# ETH_CAN_Sheet1.net
KiCad netlist of a schematic drawn in Altium Designer
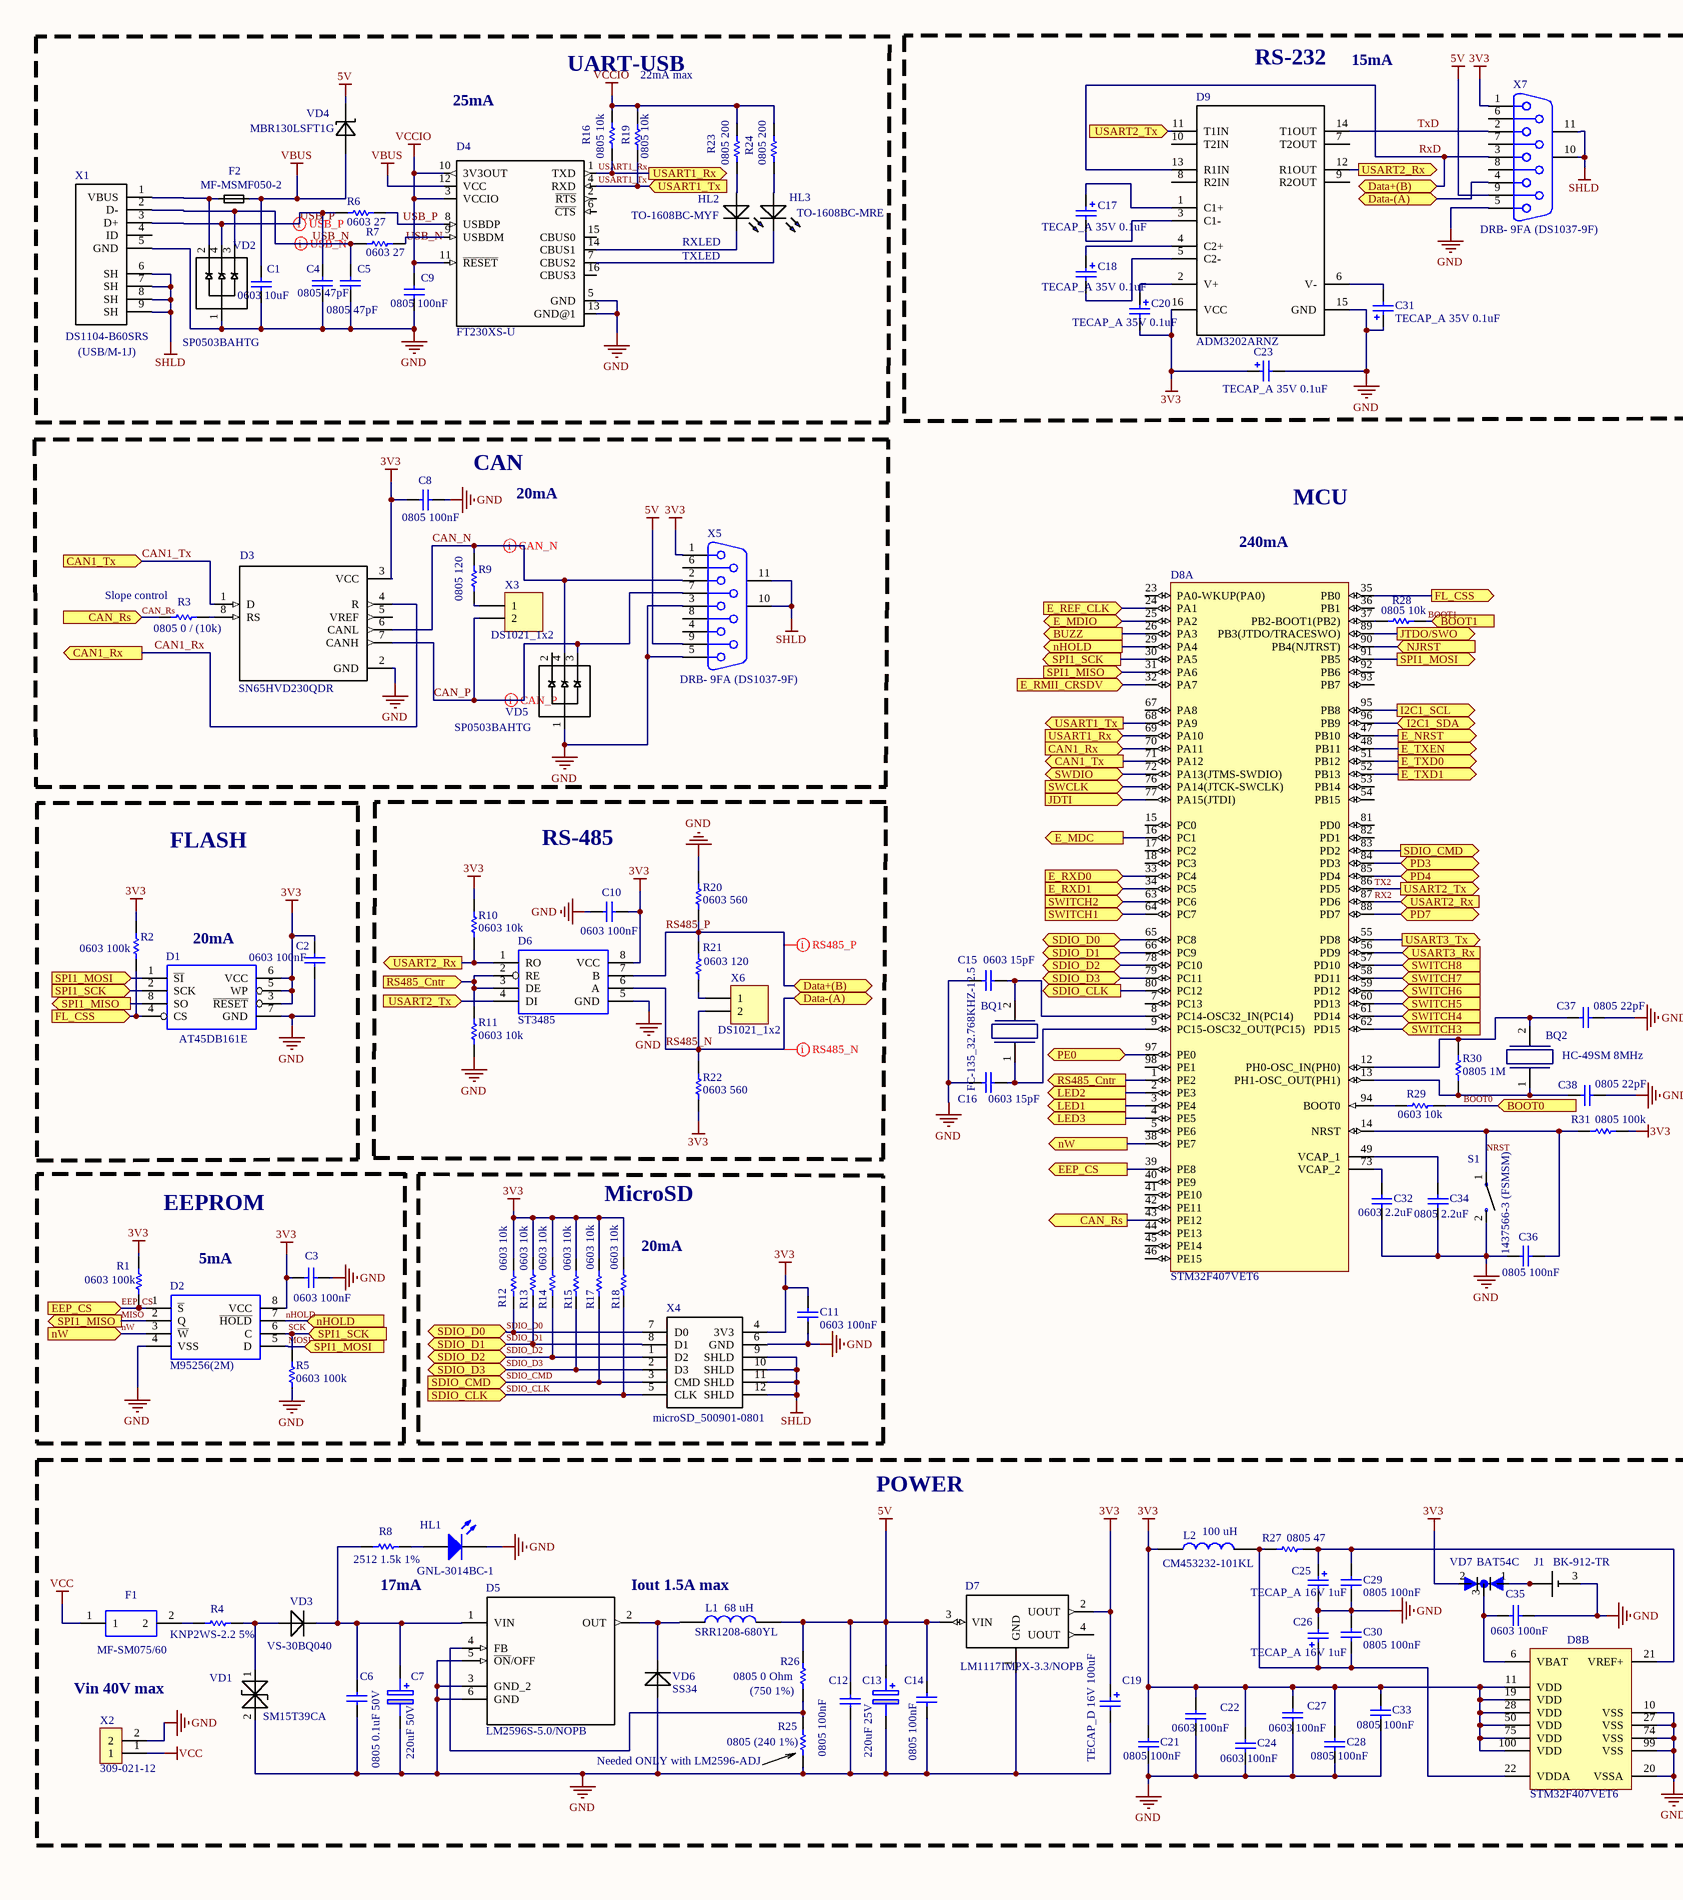
[diagram p0: ETH_CAN_Sheet1.SchDoc, left]
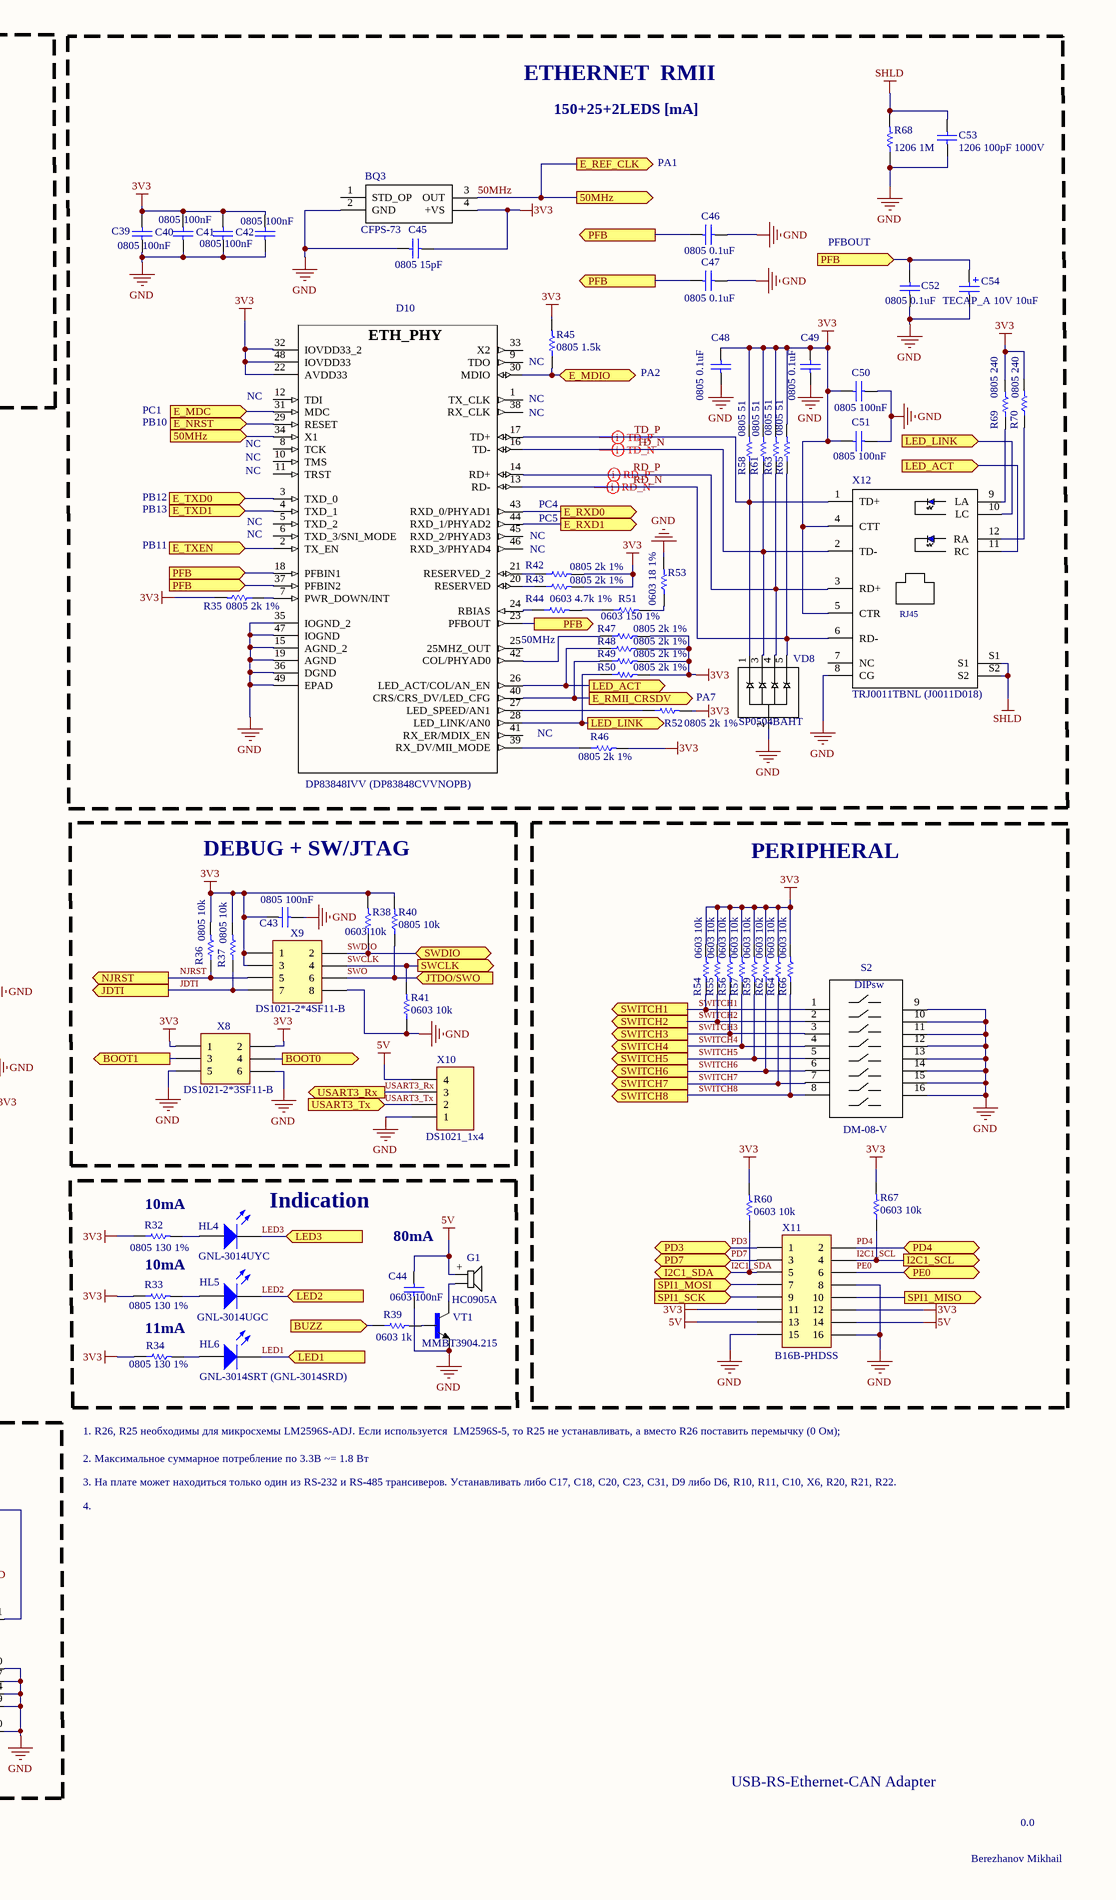
[diagram p1: ETH_CAN_Sheet1.SchDoc, right]

(export (version "E")
  (design (tool "Eeschema 10.0.6"))
  (components
    (comp (ref "BQ1")
      (value "FC-135_32.768KHZ-12.5")
      (footprint "FC-135")
      (description "Clock SMD Crystal")
      (libsource (lib "MyCompLib") (part "FC135-32768-7"))
    )
    (comp (ref "BQ2")
      (value "HC-49SM 8MHz")
      (footprint "HC49SM")
      (description "HC49SM")
      (libsource (lib "MyCompLib") (part "HC49SM"))
    )
    (comp (ref "BQ3")
      (value "CFPS-73")
      (footprint "CFPS-73")
      (description "IQD FREQUENCY PRODUCTS - SPXO018044-CFPS-73 - OSCILLATOR FREQUENCY, 50MHZ")
      (libsource (lib "MyCompLib") (part "SPXO018044CFPS-73"))
    )
    (comp (ref "C1")
      (value "0603 10uF")
      (footprint "C_SMD0603")
      (description "SMD Cap 0603")
      (libsource (lib "MyCompLib") (part "C0603"))
    )
    (comp (ref "C2")
      (value "0603 100nF")
      (footprint "C_SMD0603")
      (description "SMD Cap 0603")
      (libsource (lib "MyCompLib") (part "C0603"))
    )
    (comp (ref "C3")
      (value "0603 100nF")
      (footprint "C_SMD0603")
      (description "SMD Cap 0603")
      (libsource (lib "MyCompLib") (part "C0603"))
    )
    (comp (ref "C4")
      (value "0805 47pF")
      (footprint "C_SMD0805")
      (description "SMD Cap 0805")
      (fields (field (name "PUBLISHER") "Altium Limited"))
      (libsource (lib "MyCompLib") (part "C0805"))
    )
    (comp (ref "C5")
      (value "0805 47pF")
      (footprint "C_SMD0805")
      (description "SMD Cap 0805")
      (fields (field (name "PUBLISHER") "Altium Limited"))
      (libsource (lib "MyCompLib") (part "C0805"))
    )
    (comp (ref "C6")
      (value "0805 0.1uF 50V")
      (footprint "C_SMD0805")
      (description "SMD Cap 0805")
      (fields (field (name "PUBLISHER") "Altium Limited"))
      (libsource (lib "MyCompLib") (part "C0805"))
    )
    (comp (ref "C7")
      (value "220uF 50V")
      (footprint "SMD_ELC_CAP")
      (fields
        (field (name "MANUFACTURER_PART_NUMBER") "EEEFK1H221P")
        (field (name "RS PART NUMBER") "6294598")
      )
      (libsource (lib "MyCompLib") (part "EEEFK1H221P"))
    )
    (comp (ref "C8")
      (value "0805 100nF")
      (footprint "C_SMD0805")
      (description "SMD Cap 0805")
      (fields (field (name "PUBLISHER") "Altium Limited"))
      (libsource (lib "MyCompLib") (part "C0805"))
    )
    (comp (ref "C9")
      (value "0805 100nF")
      (footprint "C_SMD0805")
      (description "SMD Cap 0805")
      (fields (field (name "PUBLISHER") "Altium Limited"))
      (libsource (lib "MyCompLib") (part "C0805"))
    )
    (comp (ref "C10")
      (value "0603 100nF")
      (footprint "C_SMD0603")
      (description "SMD Cap 0603")
      (libsource (lib "MyCompLib") (part "C0603"))
    )
    (comp (ref "C11")
      (value "0603 100nF")
      (footprint "C_SMD0603")
      (description "SMD Cap 0603")
      (libsource (lib "MyCompLib") (part "C0603"))
    )
    (comp (ref "C12")
      (value "0805 100nF")
      (footprint "C_SMD0805")
      (description "SMD Cap 0805")
      (fields (field (name "PUBLISHER") "Altium Limited"))
      (libsource (lib "MyCompLib") (part "C0805"))
    )
    (comp (ref "C13")
      (value "220uF 25V")
      (footprint "SMD_ELC_CAP")
      (fields
        (field (name "MANUFACTURER_PART_NUMBER") "EEEFK1H221P")
        (field (name "RS PART NUMBER") "6294598")
      )
      (libsource (lib "MyCompLib") (part "EEEFK1H221P"))
    )
    (comp (ref "C14")
      (value "0805 100nF")
      (footprint "C_SMD0805")
      (description "SMD Cap 0805")
      (libsource (lib "") (part "C0805_1"))
    )
    (comp (ref "C15")
      (value "0603 15pF")
      (footprint "C_SMD0603")
      (description "SMD Cap 0603")
      (libsource (lib "MyCompLib") (part "C0603"))
    )
    (comp (ref "C16")
      (value "0603 15pF")
      (footprint "C_SMD0603")
      (description "SMD Cap 0603")
      (libsource (lib "MyCompLib") (part "C0603"))
    )
    (comp (ref "C17")
      (value "TECAP_A 35V 0.1uF")
      (footprint "TECAP_A")
      (description "Tantalum pol cap type A")
      (libsource (lib "MyCompLib") (part "TECAP_A"))
    )
    (comp (ref "C18")
      (value "TECAP_A 35V 0.1uF")
      (footprint "TECAP_A")
      (description "Tantalum pol cap type A")
      (libsource (lib "MyCompLib") (part "TECAP_A"))
    )
    (comp (ref "C19")
      (value "TECAP_D 16V 100uF")
      (footprint "TECAP_D")
      (description "Tantalum pol cap type D")
      (libsource (lib "MyCompLib") (part "TECAP_D"))
    )
    (comp (ref "C20")
      (value "TECAP_A 35V 0.1uF")
      (footprint "TECAP_A")
      (description "Tantalum pol cap type A")
      (libsource (lib "MyCompLib") (part "TECAP_A"))
    )
    (comp (ref "C21")
      (value "0805 100nF")
      (footprint "C_SMD0805")
      (description "SMD Cap 0805")
      (fields (field (name "PUBLISHER") "Altium Limited"))
      (libsource (lib "MyCompLib") (part "C0805"))
    )
    (comp (ref "C22")
      (value "0603 100nF")
      (footprint "C_SMD0603")
      (description "SMD Cap 0603")
      (libsource (lib "MyCompLib") (part "C0603"))
    )
    (comp (ref "C23")
      (value "TECAP_A 35V 0.1uF")
      (footprint "TECAP_A")
      (description "Tantalum pol cap type A")
      (libsource (lib "MyCompLib") (part "TECAP_A"))
    )
    (comp (ref "C24")
      (value "0603 100nF")
      (footprint "C_SMD0603")
      (description "SMD Cap 0603")
      (libsource (lib "MyCompLib") (part "C0603"))
    )
    (comp (ref "C25")
      (value "TECAP_A 16V 1uF")
      (footprint "TECAP_A")
      (description "Tantalum pol cap type A")
      (libsource (lib "MyCompLib") (part "TECAP_A"))
    )
    (comp (ref "C26")
      (value "TECAP_A 16V 1uF")
      (footprint "TECAP_A")
      (description "Tantalum pol cap type A")
      (libsource (lib "MyCompLib") (part "TECAP_A"))
    )
    (comp (ref "C27")
      (value "0603 100nF")
      (footprint "C_SMD0603")
      (description "SMD Cap 0603")
      (libsource (lib "MyCompLib") (part "C0603"))
    )
    (comp (ref "C28")
      (value "0805 100nF")
      (footprint "C_SMD0805")
      (description "SMD Cap 0805")
      (fields (field (name "PUBLISHER") "Altium Limited"))
      (libsource (lib "MyCompLib") (part "C0805"))
    )
    (comp (ref "C29")
      (value "0805 100nF")
      (footprint "C_SMD0805")
      (description "SMD Cap 0805")
      (fields (field (name "PUBLISHER") "Altium Limited"))
      (libsource (lib "MyCompLib") (part "C0805"))
    )
    (comp (ref "C30")
      (value "0805 100nF")
      (footprint "C_SMD0805")
      (description "SMD Cap 0805")
      (fields (field (name "PUBLISHER") "Altium Limited"))
      (libsource (lib "MyCompLib") (part "C0805"))
    )
    (comp (ref "C31")
      (value "TECAP_A 35V 0.1uF")
      (footprint "TECAP_A")
      (description "Tantalum pol cap type A")
      (libsource (lib "MyCompLib") (part "TECAP_A"))
    )
    (comp (ref "C32")
      (value "0603 2.2uF")
      (footprint "C_SMD0603")
      (description "SMD Cap 0603")
      (libsource (lib "MyCompLib") (part "C0603"))
    )
    (comp (ref "C33")
      (value "0805 100nF")
      (footprint "C_SMD0805")
      (description "SMD Cap 0805")
      (fields (field (name "PUBLISHER") "Altium Limited"))
      (libsource (lib "MyCompLib") (part "C0805"))
    )
    (comp (ref "C34")
      (value "0805 2.2uF")
      (footprint "C_SMD0805")
      (description "SMD Cap 0805")
      (fields (field (name "PUBLISHER") "Altium Limited"))
      (libsource (lib "MyCompLib") (part "C0805"))
    )
    (comp (ref "C35")
      (value "0603 100nF")
      (footprint "C_SMD0603")
      (description "SMD Cap 0603")
      (libsource (lib "MyCompLib") (part "C0603"))
    )
    (comp (ref "C36")
      (value "0805 100nF")
      (footprint "C_SMD0805")
      (description "SMD Cap 0805")
      (fields (field (name "PUBLISHER") "Altium Limited"))
      (libsource (lib "MyCompLib") (part "C0805"))
    )
    (comp (ref "C37")
      (value "0805 22pF")
      (footprint "C_SMD0805")
      (description "SMD Cap 0805")
      (fields (field (name "PUBLISHER") "Altium Limited"))
      (libsource (lib "MyCompLib") (part "C0805"))
    )
    (comp (ref "C38")
      (value "0805 22pF")
      (footprint "C_SMD0805")
      (description "SMD Cap 0805")
      (fields (field (name "PUBLISHER") "Altium Limited"))
      (libsource (lib "MyCompLib") (part "C0805"))
    )
    (comp (ref "C39")
      (value "0805 100nF")
      (footprint "C_SMD0805")
      (description "SMD Cap 0805")
      (fields (field (name "PUBLISHER") "Altium Limited"))
      (libsource (lib "MyCompLib") (part "C0805"))
    )
    (comp (ref "C40")
      (value "0805 100nF")
      (footprint "C_SMD0805")
      (description "SMD Cap 0805")
      (fields (field (name "PUBLISHER") "Altium Limited"))
      (libsource (lib "MyCompLib") (part "C0805"))
    )
    (comp (ref "C41")
      (value "0805 100nF")
      (footprint "C_SMD0805")
      (description "SMD Cap 0805")
      (fields (field (name "PUBLISHER") "Altium Limited"))
      (libsource (lib "MyCompLib") (part "C0805"))
    )
    (comp (ref "C42")
      (value "0805 100nF")
      (footprint "C_SMD0805")
      (description "SMD Cap 0805")
      (fields (field (name "PUBLISHER") "Altium Limited"))
      (libsource (lib "MyCompLib") (part "C0805"))
    )
    (comp (ref "C43")
      (value "0805 100nF")
      (footprint "C_SMD0805")
      (description "SMD Cap 0805")
      (fields (field (name "PUBLISHER") "Altium Limited"))
      (libsource (lib "MyCompLib") (part "C0805"))
    )
    (comp (ref "C44")
      (value "0603 100nF")
      (footprint "C_SMD0603")
      (description "SMD Cap 0603")
      (libsource (lib "MyCompLib") (part "C0603"))
    )
    (comp (ref "C45")
      (value "0805 15pF")
      (footprint "C_SMD0805")
      (description "SMD Cap 0805")
      (fields (field (name "PUBLISHER") "Altium Limited"))
      (libsource (lib "MyCompLib") (part "C0805"))
    )
    (comp (ref "C46")
      (value "0805 0.1uF")
      (footprint "C_SMD0805")
      (description "SMD Cap 0805")
      (fields (field (name "PUBLISHER") "Altium Limited"))
      (libsource (lib "MyCompLib") (part "C0805"))
    )
    (comp (ref "C47")
      (value "0805 0.1uF")
      (footprint "C_SMD0805")
      (description "SMD Cap 0805")
      (fields (field (name "PUBLISHER") "Altium Limited"))
      (libsource (lib "MyCompLib") (part "C0805"))
    )
    (comp (ref "C48")
      (value "0805 0.1uF")
      (footprint "C_SMD0805")
      (description "SMD Cap 0805")
      (fields (field (name "PUBLISHER") "Altium Limited"))
      (libsource (lib "MyCompLib") (part "C0805"))
    )
    (comp (ref "C49")
      (value "0805 0.1uF")
      (footprint "C_SMD0805")
      (description "SMD Cap 0805")
      (fields (field (name "PUBLISHER") "Altium Limited"))
      (libsource (lib "MyCompLib") (part "C0805"))
    )
    (comp (ref "C50")
      (value "0805 100nF")
      (footprint "C_SMD0805")
      (description "SMD Cap 0805")
      (fields (field (name "PUBLISHER") "Altium Limited"))
      (libsource (lib "MyCompLib") (part "C0805"))
    )
    (comp (ref "C51")
      (value "0805 100nF")
      (footprint "C_SMD0805")
      (description "SMD Cap 0805")
      (fields (field (name "PUBLISHER") "Altium Limited"))
      (libsource (lib "MyCompLib") (part "C0805"))
    )
    (comp (ref "C52")
      (value "0805 0.1uF")
      (footprint "C_SMD0805")
      (description "SMD Cap 0805")
      (fields (field (name "PUBLISHER") "Altium Limited"))
      (libsource (lib "MyCompLib") (part "C0805"))
    )
    (comp (ref "C53")
      (value "1206 100pF 1000V")
      (footprint "CAP SMD1206")
      (description "SMD Cap 1206")
      (fields (field (name "PUBLISHER") "Altium Limited"))
      (libsource (lib "MyCompLib") (part "C1206"))
    )
    (comp (ref "C54")
      (value "TECAP_A 10V 10uF")
      (footprint "TECAP_A")
      (description "Tantalum pol cap type A")
      (libsource (lib "MyCompLib") (part "TECAP_A"))
    )
    (comp (ref "D1")
      (value "AT45DB161E")
      (footprint "SOIC8 (SO-8)")
      (description "SPI FLASH 16Mbit(528 bytes x 4096 pages)")
      (libsource (lib "MyCompLib") (part "AT45DB161E"))
    )
    (comp (ref "D2")
      (value "M95256(2M)")
      (footprint "SOIC8 (SO-8)")
      (description "M95256-WMN6TP, Serial EEPROM Memory 256kbit, Serial-SPI, 60ns 2.5  5.5 V, 8-Pin SOIC")
      (libsource (lib "MyCompLib") (part "M95256(2M)-WMN6TP"))
    )
    (comp (ref "D3")
      (value "SN65HVD230QDR")
      (footprint "SOIC-12")
      (description "3.3-V CAN Transceiver with Standby Mode 8-SOIC -40 to 125")
      (fields (field (name "MF") "Texas Instruments"))
      (libsource (lib "MyCompLib") (part "SN65HVD230QDR"))
    )
    (comp (ref "D4")
      (value "FT230XS-U")
      (footprint "SSOP16")
      (description "FT230XS-U, USB Controller, 3MBd, USB 1.1, USB 2.0, 5 V, 16-Pin SSOP")
      (fields (field (name "MF") "FTDI,"))
      (libsource (lib "MyCompLib") (part "FT230XS-U"))
    )
    (comp (ref "D5")
      (value "LM2596S-5.0/NOPB")
      (footprint "TO263-5")
      (description "SIMPLE SWITCHER&#174; 4.5V to 40V, 3A Low Component Count Step-Down Regulator")
      (libsource (lib "MyCompLib") (part "LM2596S"))
    )
    (comp (ref "D6")
      (value "ST3485")
      (footprint "SOIC8 (SO-8)")
      (description "3.3 V low power transceiver for RS-485")
      (libsource (lib "MyCompLib") (part "ST3485"))
    )
    (comp (ref "D7")
      (value "LM1117IMPX-3.3/NOPB")
      (footprint "SOT223")
      (description "Линейный регулятор с низким падением напряжения, 3.3В")
      (libsource (lib "MyCompLib") (part "LM1117-3.3"))
    )
    (comp (ref "D8")
      (value "STM32F407VET6")
      (footprint "STM-LQFP100_N")
      (fields (field (name "MANUFACTURER") "STMicroelectronics"))
      (libsource (lib "STMicroelectronics STM32 F4") (part "STM32F407VET6"))
    )
    (comp (ref "D9")
      (value "ADM3202ARNZ")
      (footprint "SOIC-16")
      (description "3.3V SMD RS232-UART")
      (libsource (lib "MyCompLib") (part "ADM3202ARNZ"))
    )
    (comp (ref "D10")
      (value "DP83848IVV (DP83848CVVNOPB)")
      (footprint "QFP48")
      (description "ETH Transciever")
      (libsource (lib "MyCompLib") (part "DP83848CVVNOPB"))
    )
    (comp (ref "F1")
      (value "MF-SM075/60")
      (footprint "MF-SM075/60")
      (libsource (lib "MyCompLib") (part "MF-SM075/60"))
    )
    (comp (ref "F2")
      (value "MF-MSMF050-2")
      (footprint "FUSE1812x0")
      (description "PTC Resettable Fuse 0.5A_hold_ 1A_trip_ 15V 100A 0.8W 0.15s 0.15Ohm SMD Solder Pad 1812 T/R")
      (libsource (lib "MyCompLib") (part "MF-MSMF050-2"))
    )
    (comp (ref "G1")
      (value "HC0905A")
      (footprint "HC090xA")
      (description "Buzzer 5V 80mA h=5mm d=9.5mm 3200Hz")
      (libsource (lib "MyCompLib") (part "HC0905A"))
    )
    (comp (ref "HL1")
      (value "GNL-3014BC-1")
      (footprint "LED3mm")
      (libsource (lib "MyCompLib") (part "LED_0_25_4"))
    )
    (comp (ref "HL2")
      (value "TO-1608BC-MYF")
      (footprint "LED_SMD1608GREEN")
      (description "TO-1608BC-BF \\  TO-1608BC-MRE")
      (libsource (lib "MyCompLib") (part "LED_SMD"))
    )
    (comp (ref "HL3")
      (value "TO-1608BC-MRE")
      (footprint "LED_SMD1608")
      (description "TO-1608BC-BF \\  TO-1608BC-MRE")
      (libsource (lib "MyCompLib") (part "LED_SMD"))
    )
    (comp (ref "HL4")
      (value "GNL-3014UYC")
      (footprint "LED3mm")
      (description "Светодиод желтый 25° d=3мм 1000мКд 589нМ (Yellow)")
      (libsource (lib "MyCompLib") (part "LED_0_25_4"))
    )
    (comp (ref "HL5")
      (value "GNL-3014UGC")
      (footprint "LED3mm")
      (description "Светодиод зеленый 25° d=3мм 1200мКд 572нМ (Green)")
      (libsource (lib "MyCompLib") (part "LED_0_25_4"))
    )
    (comp (ref "HL6")
      (value "GNL-3014SRT (GNL-3014SRD)")
      (footprint "LED3mm")
      (description "Светодиод красный 20° d=3мм 200мКд 660нМ (Red)")
      (libsource (lib "MyCompLib") (part "LED_0_25_4"))
    )
    (comp (ref "J1")
      (value "BK-912-TR")
      (footprint "BK-912-TR")
      (description "Holder Coin Cell 20mm Smd")
      (libsource (lib "MyCompLib") (part "BK-912-TR"))
    )
    (comp (ref "L1")
      (value "SRR1208-680YL")
      (footprint "SRR1208")
      (description "Fixed Inductors 330uH 10% SMD 1208")
      (fields (field (name "MANUFACTURER_PART_NUMBER") "SRR1208-682KL"))
      (libsource (lib "MyCompLib") (part "SRR1208-682KL"))
    )
    (comp (ref "L2")
      (value "CM453232-101KL")
      (footprint "CM453232-101KL")
      (description "BOURNS - CM453232-101KL - INDUCTOR, 4532 CASE, 100UH")
      (fields
        (field (name "MANUFACTURER_PART_NUMBER") "CM453232-471KL")
        (field (name "RS PART NUMBER") "6934353")
      )
      (libsource (lib "MyCompLib") (part "CM453232-471KL"))
    )
    (comp (ref "R1")
      (value "0603 100k")
      (footprint "R_SMD0603")
      (description "SMD Res 0603")
      (libsource (lib "MyCompLib") (part "R0603"))
    )
    (comp (ref "R2")
      (value "0603 100k")
      (footprint "R_SMD0603")
      (description "SMD Res 0603")
      (libsource (lib "MyCompLib") (part "R0603"))
    )
    (comp (ref "R3")
      (value "0805 0 / (10k)")
      (footprint "R_SMD0805")
      (description "SMD Res 0805")
      (libsource (lib "MyCompLib") (part "R0805"))
    )
    (comp (ref "R4")
      (value "KNP2WS-2.2 5%")
      (footprint "KNP2WS")
      (description "Резисторы с проволочной обмоткой – сквозное отверстие 2.2ohm 2W 5%")
      (libsource (lib "MyCompLib") (part "KNP2WS"))
    )
    (comp (ref "R5")
      (value "0603 100k")
      (footprint "R_SMD0603")
      (description "SMD Res 0603")
      (libsource (lib "MyCompLib") (part "R0603"))
    )
    (comp (ref "R6")
      (value "0603 27")
      (footprint "R_SMD0603")
      (description "SMD Res 0603")
      (libsource (lib "MyCompLib") (part "R0603"))
    )
    (comp (ref "R7")
      (value "0603 27")
      (footprint "R_SMD0603")
      (description "SMD Res 0603")
      (libsource (lib "MyCompLib") (part "R0603"))
    )
    (comp (ref "R8")
      (value "2512 1.5k 1%")
      (footprint "R_SMD2512")
      (description "SMD Res 2512")
      (libsource (lib "MyCompLib") (part "R2512"))
    )
    (comp (ref "R9")
      (value "0805 120")
      (footprint "R_SMD0805")
      (description "SMD Res 0805")
      (libsource (lib "MyCompLib") (part "R0805"))
    )
    (comp (ref "R10")
      (value "0603 10k")
      (footprint "R_SMD0603")
      (description "SMD Res 0603")
      (libsource (lib "MyCompLib") (part "R0603"))
    )
    (comp (ref "R11")
      (value "0603 10k")
      (footprint "R_SMD0603")
      (description "SMD Res 0603")
      (libsource (lib "MyCompLib") (part "R0603"))
    )
    (comp (ref "R12")
      (value "0603 10k")
      (footprint "R_SMD0603")
      (description "SMD Res 0603")
      (libsource (lib "MyCompLib") (part "R0603"))
    )
    (comp (ref "R13")
      (value "0603 10k")
      (footprint "R_SMD0603")
      (description "SMD Res 0603")
      (libsource (lib "MyCompLib") (part "R0603"))
    )
    (comp (ref "R14")
      (value "0603 10k")
      (footprint "R_SMD0603")
      (description "SMD Res 0603")
      (libsource (lib "MyCompLib") (part "R0603"))
    )
    (comp (ref "R15")
      (value "0603 10k")
      (footprint "R_SMD0603")
      (description "SMD Res 0603")
      (libsource (lib "MyCompLib") (part "R0603"))
    )
    (comp (ref "R16")
      (value "0805 10k")
      (footprint "R_SMD0805")
      (description "SMD Res 0805")
      (libsource (lib "MyCompLib") (part "R0805"))
    )
    (comp (ref "R17")
      (value "0603 10k")
      (footprint "R_SMD0603")
      (description "SMD Res 0603")
      (libsource (lib "MyCompLib") (part "R0603"))
    )
    (comp (ref "R18")
      (value "0603 10k")
      (footprint "R_SMD0603")
      (description "SMD Res 0603")
      (libsource (lib "MyCompLib") (part "R0603"))
    )
    (comp (ref "R19")
      (value "0805 10k")
      (footprint "R_SMD0805")
      (description "SMD Res 0805")
      (libsource (lib "MyCompLib") (part "R0805"))
    )
    (comp (ref "R20")
      (value "0603 560")
      (footprint "R_SMD0603")
      (description "SMD Res 0603")
      (libsource (lib "MyCompLib") (part "R0603"))
    )
    (comp (ref "R21")
      (value "0603 120")
      (footprint "R_SMD0603")
      (description "SMD Res 0603")
      (libsource (lib "MyCompLib") (part "R0603"))
    )
    (comp (ref "R22")
      (value "0603 560")
      (footprint "R_SMD0603")
      (description "SMD Res 0603")
      (libsource (lib "MyCompLib") (part "R0603"))
    )
    (comp (ref "R23")
      (value "0805 200")
      (footprint "R_SMD0805")
      (description "SMD Res 0805")
      (libsource (lib "MyCompLib") (part "R0805"))
    )
    (comp (ref "R24")
      (value "0805 200")
      (footprint "R_SMD0805")
      (description "SMD Res 0805")
      (libsource (lib "MyCompLib") (part "R0805"))
    )
    (comp (ref "R25")
      (value "0805 (240 1%)")
      (footprint "R_SMD0805")
      (description "SMD Res 0805")
      (libsource (lib "MyCompLib") (part "R0805"))
    )
    (comp (ref "R26")
      (value "0805 0 Ohm")
      (footprint "C_SMD0805")
      (description "SMD Res 0805")
      (libsource (lib "MyCompLib") (part "R0805"))
    )
    (comp (ref "R27")
      (value "0805 47")
      (footprint "R_SMD0805")
      (description "SMD Res 0805")
      (libsource (lib "MyCompLib") (part "R0805"))
    )
    (comp (ref "R28")
      (value "0805 10k")
      (footprint "R_SMD0805")
      (description "SMD Res 0805")
      (libsource (lib "MyCompLib") (part "R0805"))
    )
    (comp (ref "R29")
      (value "0603 10k")
      (footprint "R_SMD0603")
      (description "SMD Res 0603")
      (libsource (lib "MyCompLib") (part "R0603"))
    )
    (comp (ref "R30")
      (value "0805 1M")
      (footprint "R_SMD0805")
      (description "SMD Res 0805")
      (libsource (lib "MyCompLib") (part "R0805"))
    )
    (comp (ref "R31")
      (value "0805 100k")
      (footprint "C_SMD0805")
      (description "SMD Res 0805")
      (libsource (lib "MyCompLib") (part "R0805"))
    )
    (comp (ref "R32")
      (value "0805 130 1%")
      (footprint "R_SMD0805")
      (description "SMD Res 0805")
      (libsource (lib "MyCompLib") (part "R0805"))
    )
    (comp (ref "R33")
      (value "0805 130 1%")
      (footprint "R_SMD0805")
      (description "SMD Res 0805")
      (libsource (lib "MyCompLib") (part "R0805"))
    )
    (comp (ref "R34")
      (value "0805 130 1%")
      (footprint "R_SMD0805")
      (description "SMD Res 0805")
      (libsource (lib "MyCompLib") (part "R0805"))
    )
    (comp (ref "R35")
      (value "0805 2k 1%")
      (footprint "R_SMD0805")
      (description "SMD Res 0805")
      (libsource (lib "MyCompLib") (part "R0805"))
    )
    (comp (ref "R36")
      (value "0805 10k")
      (footprint "R_SMD0805")
      (description "SMD Res 0805")
      (libsource (lib "MyCompLib") (part "R0805"))
    )
    (comp (ref "R37")
      (value "0805 10k")
      (footprint "R_SMD0805")
      (description "SMD Res 0805")
      (libsource (lib "MyCompLib") (part "R0805"))
    )
    (comp (ref "R38")
      (value "0603 10k")
      (footprint "R_SMD0603")
      (description "SMD Res 0603")
      (libsource (lib "MyCompLib") (part "R0603"))
    )
    (comp (ref "R39")
      (value "0603 1k")
      (footprint "R_SMD0603")
      (description "SMD Res 0603")
      (libsource (lib "MyCompLib") (part "R0603"))
    )
    (comp (ref "R40")
      (value "0805 10k")
      (footprint "R_SMD0805")
      (description "SMD Res 0805")
      (libsource (lib "MyCompLib") (part "R0805"))
    )
    (comp (ref "R41")
      (value "0603 10k")
      (footprint "R_SMD0603")
      (description "SMD Res 0603")
      (libsource (lib "MyCompLib") (part "R0603"))
    )
    (comp (ref "R42")
      (value "0805 2k 1%")
      (footprint "R_SMD0805")
      (description "SMD Res 0805")
      (libsource (lib "MyCompLib") (part "R0805"))
    )
    (comp (ref "R43")
      (value "0805 2k 1%")
      (footprint "R_SMD0805")
      (description "SMD Res 0805")
      (libsource (lib "MyCompLib") (part "R0805"))
    )
    (comp (ref "R44")
      (value "0603 4.7k 1%")
      (footprint "R_SMD0603")
      (description "SMD Res 0603")
      (libsource (lib "MyCompLib") (part "R0603"))
    )
    (comp (ref "R45")
      (value "0805 1.5k")
      (footprint "R_SMD0805")
      (description "SMD Res 0805")
      (libsource (lib "MyCompLib") (part "R0805"))
    )
    (comp (ref "R46")
      (value "0805 2k 1%")
      (footprint "R_SMD0805")
      (description "SMD Res 0805")
      (libsource (lib "MyCompLib") (part "R0805"))
    )
    (comp (ref "R47")
      (value "0805 2k 1%")
      (footprint "R_SMD0805")
      (description "SMD Res 0805")
      (libsource (lib "MyCompLib") (part "R0805"))
    )
    (comp (ref "R48")
      (value "0805 2k 1%")
      (footprint "R_SMD0805")
      (description "SMD Res 0805")
      (libsource (lib "MyCompLib") (part "R0805"))
    )
    (comp (ref "R49")
      (value "0805 2k 1%")
      (footprint "R_SMD0805")
      (description "SMD Res 0805")
      (libsource (lib "MyCompLib") (part "R0805"))
    )
    (comp (ref "R50")
      (value "0805 2k 1%")
      (footprint "R_SMD0805")
      (description "SMD Res 0805")
      (libsource (lib "MyCompLib") (part "R0805"))
    )
    (comp (ref "R51")
      (value "0603 150 1%")
      (footprint "R_SMD0603")
      (description "SMD Res 0603")
      (libsource (lib "MyCompLib") (part "R0603"))
    )
    (comp (ref "R52")
      (value "0805 2k 1%")
      (footprint "R_SMD0805")
      (description "SMD Res 0805")
      (libsource (lib "MyCompLib") (part "R0805"))
    )
    (comp (ref "R53")
      (value "0603 18 1%")
      (footprint "R_SMD0603")
      (description "SMD Res 0603")
      (libsource (lib "MyCompLib") (part "R0603"))
    )
    (comp (ref "R54")
      (value "0603 10k")
      (footprint "R_SMD0603")
      (description "SMD Res 0603")
      (libsource (lib "MyCompLib") (part "R0603"))
    )
    (comp (ref "R55")
      (value "0603 10k")
      (footprint "R_SMD0603")
      (description "SMD Res 0603")
      (libsource (lib "MyCompLib") (part "R0603"))
    )
    (comp (ref "R56")
      (value "0603 10k")
      (footprint "R_SMD0603")
      (description "SMD Res 0603")
      (libsource (lib "MyCompLib") (part "R0603"))
    )
    (comp (ref "R57")
      (value "0603 10k")
      (footprint "R_SMD0603")
      (description "SMD Res 0603")
      (libsource (lib "MyCompLib") (part "R0603"))
    )
    (comp (ref "R58")
      (value "0805 51")
      (footprint "R_SMD0805")
      (description "SMD Res 0805")
      (libsource (lib "MyCompLib") (part "R0805"))
    )
    (comp (ref "R59")
      (value "0603 10k")
      (footprint "R_SMD0603")
      (description "SMD Res 0603")
      (libsource (lib "MyCompLib") (part "R0603"))
    )
    (comp (ref "R60")
      (value "0603 10k")
      (footprint "R_SMD0603")
      (description "SMD Res 0603")
      (libsource (lib "MyCompLib") (part "R0603"))
    )
    (comp (ref "R61")
      (value "0805 51")
      (footprint "R_SMD0805")
      (description "SMD Res 0805")
      (libsource (lib "MyCompLib") (part "R0805"))
    )
    (comp (ref "R62")
      (value "0603 10k")
      (footprint "R_SMD0603")
      (description "SMD Res 0603")
      (libsource (lib "MyCompLib") (part "R0603"))
    )
    (comp (ref "R63")
      (value "0805 51")
      (footprint "R_SMD0805")
      (description "SMD Res 0805")
      (libsource (lib "MyCompLib") (part "R0805"))
    )
    (comp (ref "R64")
      (value "0603 10k")
      (footprint "R_SMD0603")
      (description "SMD Res 0603")
      (libsource (lib "MyCompLib") (part "R0603"))
    )
    (comp (ref "R65")
      (value "0805 51")
      (footprint "R_SMD0805")
      (description "SMD Res 0805")
      (libsource (lib "MyCompLib") (part "R0805"))
    )
    (comp (ref "R66")
      (value "0603 10k")
      (footprint "R_SMD0603")
      (description "SMD Res 0603")
      (libsource (lib "MyCompLib") (part "R0603"))
    )
    (comp (ref "R67")
      (value "0603 10k")
      (footprint "R_SMD0603")
      (description "SMD Res 0603")
      (libsource (lib "MyCompLib") (part "R0603"))
    )
    (comp (ref "R68")
      (value "1206 1M")
      (footprint "R_SMD1206")
      (description "SMD Res 1206")
      (libsource (lib "MyCompLib") (part "R1206"))
    )
    (comp (ref "R69")
      (value "0805 240")
      (footprint "R_SMD0805")
      (description "SMD Res 0805")
      (libsource (lib "MyCompLib") (part "R0805"))
    )
    (comp (ref "R70")
      (value "0805 240")
      (footprint "R_SMD0805")
      (description "SMD Res 0805")
      (libsource (lib "MyCompLib") (part "R0805"))
    )
    (comp (ref "S1")
      (value "1437566-3 (FSMSM)")
      (footprint "1437566-3")
      (description "FSMSM=3.5X6 SMT TACT")
      (fields (field (name "MP") "1437566-3") (field (name "MF") "TE Connectivity"))
      (libsource (lib "MyCompLib") (part "1437566-3"))
    )
    (comp (ref "S2")
      (value "DM-08-V")
      (footprint "DM-08-V")
      (description "SMD DIPSWITCH8")
      (libsource (lib "MyCompLib") (part "DM-08-V"))
    )
    (comp (ref "VD1")
      (value "SM15T39CA")
      (footprint "DO214AB SMC")
      (description "TVS Diode Bi-Directional SM15T39CA 69.7V, 1500W, SMC 2-Pin")
      (libsource (lib "MyCompLib") (part "SM15T39CA"))
    )
    (comp (ref "VD2")
      (value "SP0503BAHTG")
      (footprint "SP0503BAHTG")
      (description "SP050xBA Series 8 V 30 pF Uni-Directional SMT TVS Avalanche Diode Array SOT-143")
      (fields (field (name "MF") "Littelfuse Inc."))
      (libsource (lib "MyCompLib") (part "SP0503BAHTG"))
    )
    (comp (ref "VD3")
      (value "VS-30BQ040")
      (footprint "DO214AB SMC")
      (description "VS-30BQ040-M3/9AT Vishay VS-30BQ040-M3/9AT, SMT Schottky Diode, 40V 4A, 2-Pin DO-214AB")
      (libsource (lib "MyCompLib") (part "VS-30BQ040"))
    )
    (comp (ref "VD4")
      (value "MBR130LSFT1G")
      (footprint "SOD-123FL")
      (description "Schottky Barrier Diodes, 1A to 2A, ON Semiconductor")
      (libsource (lib "MyCompLib") (part "MBR130LSFT1G"))
    )
    (comp (ref "VD5")
      (value "SP0503BAHTG")
      (footprint "SP0503BAHTG")
      (description "SP050xBA Series 8 V 30 pF Uni-Directional SMT TVS Avalanche Diode Array SOT-143")
      (fields (field (name "MF") "Littelfuse Inc."))
      (libsource (lib "MyCompLib") (part "SP0503BAHTG"))
    )
    (comp (ref "VD6")
      (value "SS34")
      (footprint "DO214AB SMC")
      (description "Rectifier, Schottky; DO-214AB; 3.0A IF; 0.75V; 40V; 100A IFRM; 10000V/us; 1000pF")
      (libsource (lib "MyCompLib") (part "SS34"))
    )
    (comp (ref "VD7")
      (value "BAT54C")
      (footprint "BAT54C_SOT23-3")
      (description "Small Signal Schottky Diode, Dual Common Cathode, 30 V, 200 mA, 400 mV, 600 mA, 125 C")
      (libsource (lib "MyCompLib") (part "BAT54C"))
    )
    (comp (ref "VD8")
      (value "SP0504BAHT")
      (footprint "SOT23-5")
      (description "TVS Diode-4")
      (libsource (lib "MyCompLib") (part "SP0504BAHT"))
    )
    (comp (ref "VT1")
      (value "MMBT3904.215")
      (footprint "SOT23")
      (description "Транзистор NPN 40В 0.2А [SOT-23-3]")
      (libsource (lib "MyCompLib") (part "MMBT3904.215"))
    )
    (comp (ref "X1")
      (value "DS1104-B60SRS")
      (footprint "MUSB-05-S-B-SM")
      (description "Conn Mini USB 2.0 Type B RCP 5 POS 0.8mm Solder RA SMD 5 Terminal 1 Port Tray")
      (libsource (lib "MyCompLib") (part "MSUB-05 (DS1104)"))
    )
    (comp (ref "X2")
      (value "309-021-12")
      (footprint "390-021-12")
      (description "DG390-5.0-02P (XY118-2P-05) Зажимной Клеммник 2-контактный, 5.0мм угловой")
      (libsource (lib "MyCompLib") (part "309-021-12"))
    )
    (comp (ref "X3")
      (value "DS1021_1x2")
      (footprint "PLD2")
      (description "Вилка штыревая 2.54мм 1x2 прямая тип1")
      (libsource (lib "MyCompLib") (part "DS1021_1x2"))
    )
    (comp (ref "X4")
      (value "microSD_500901-0801")
      (footprint "5009001-0801")
      (description "TransFlash Memory Card,1.1mm hinge type TransFlash Memory Card,1.1mm hinge type")
      (libsource (lib "MyCompLib") (part "microSD_500901-0801"))
    )
    (comp (ref "X5")
      (value "DRB- 9FA (DS1037-9F)")
      (footprint "DRB- 9FA")
      (libsource (lib "MyCompLib") (part "DRB- 9FA (DS1037-9F)"))
    )
    (comp (ref "X6")
      (value "DS1021_1x2")
      (footprint "PLD2")
      (description "Вилка штыревая 2.54мм 1x2 прямая тип1")
      (libsource (lib "MyCompLib") (part "DS1021_1x2"))
    )
    (comp (ref "X7")
      (value "DRB- 9FA (DS1037-9F)")
      (footprint "DRB- 9FA")
      (libsource (lib "MyCompLib") (part "DRB- 9FA (DS1037-9F)"))
    )
    (comp (ref "X8")
      (value "DS1021-2*3SF11-B")
      (footprint "PLD2-3")
      (description "Вилка штыревая 2.54мм 2x3 прямая тип1")
      (libsource (lib "MyCompLib") (part "DS1021_2x3"))
    )
    (comp (ref "X9")
      (value "DS1021-2*4SF11-B")
      (footprint "PLD2-4")
      (description "Вилка штыревая 2.54мм 2x4 прямая тип1")
      (libsource (lib "MyCompLib") (part "DS1021_2x4"))
    )
    (comp (ref "X10")
      (value "DS1021_1x4")
      (footprint "PLD1X4")
      (description "Вилка штыревая 2.54мм 1x4 прямая тип1")
      (libsource (lib "MyCompLib") (part "DS1021_1x4"))
    )
    (comp (ref "X11")
      (value "B16B-PHDSS")
      (footprint "PHD16")
      (description "HEADER, PHD, TOP, 16WAY, 2MM; Pitch Spacing:2mm; No. of Contacts:16Contacts;")
      (libsource (lib "MyCompLib") (part "B16B-PHDSS"))
    )
    (comp (ref "X12")
      (value "TRJ0011TBNL (J0011D018)")
      (footprint "J0011D018")
      (description "Conn RJ-45 F 8 POS 2.54mm Solder RA Thru-Hole 12 Terminal 1 Port Cat 5/Cat 6")
      (libsource (lib "MyCompLib") (part "RJ45 J0011D018"))
    )
  )
  (nets
    (net (code "1") (name "/50MHz") (class "Default")
      (node (ref "BQ3") (pin "3") (pinfunction "OUT_3") (pintype "passive"))
      (node (ref "D10") (pin "34") (pinfunction "X1_34") (pintype "input"))
      (node (ref "D8") (pin "24") (pinfunction "PA1_24") (pintype "bidirectional"))
    )
    (net (code "2") (name "/BOOT0") (class "Default")
      (node (ref "R29") (pin "2") (pinfunction "2_2") (pintype "passive"))
      (node (ref "X8") (pin "4") (pinfunction "4_4") (pintype "passive"))
    )
    (net (code "3") (name "/BOOT1") (class "Default")
      (node (ref "R28") (pin "2") (pinfunction "2_2") (pintype "passive"))
      (node (ref "X8") (pin "3") (pinfunction "3_3") (pintype "passive"))
    )
    (net (code "4") (name "/BUZZ") (class "Default")
      (node (ref "D8") (pin "26") (pinfunction "PA3_26") (pintype "bidirectional"))
      (node (ref "R39") (pin "1") (pinfunction "1_1") (pintype "passive"))
    )
    (net (code "5") (name "/CAN1_Rx") (class "Default")
      (node (ref "D3") (pin "4") (pinfunction "R_4") (pintype "output"))
      (node (ref "D8") (pin "70") (pinfunction "PA11_70") (pintype "bidirectional"))
    )
    (net (code "6") (name "/CAN1_Tx") (class "Default")
      (node (ref "D3") (pin "1") (pinfunction "D_1") (pintype "input"))
      (node (ref "D8") (pin "71") (pinfunction "PA12_71") (pintype "bidirectional"))
    )
    (net (code "7") (name "/CAN_N") (class "Default")
      (node (ref "D3") (pin "6") (pinfunction "CANL_6") (pintype "output"))
      (node (ref "R9") (pin "1") (pinfunction "1_1") (pintype "passive"))
      (node (ref "VD5") (pin "4") (pinfunction "C_4") (pintype "passive"))
      (node (ref "X5") (pin "2") (pinfunction "2_2") (pintype "passive"))
    )
    (net (code "8") (name "/CAN_P") (class "Default")
      (node (ref "D3") (pin "7") (pinfunction "CANH_7") (pintype "output"))
      (node (ref "VD5") (pin "3") (pinfunction "B_3") (pintype "passive"))
      (node (ref "X3") (pin "2") (pinfunction "2_2") (pintype "passive"))
      (node (ref "X5") (pin "7") (pinfunction "7_7") (pintype "passive"))
    )
    (net (code "9") (name "/CAN_Rs") (class "Default")
      (node (ref "D8") (pin "43") (pinfunction "PE12_43") (pintype "bidirectional"))
      (node (ref "R3") (pin "2") (pinfunction "2_2") (pintype "passive"))
    )
    (net (code "10") (name "/EEP_CS") (class "Default")
      (node (ref "D2") (pin "1") (pinfunction "S_1") (pintype "passive"))
      (node (ref "D8") (pin "39") (pinfunction "PE8_39") (pintype "bidirectional"))
      (node (ref "R1") (pin "1") (pinfunction "1_1") (pintype "passive"))
    )
    (net (code "11") (name "/E_MDC") (class "Default")
      (node (ref "D10") (pin "31") (pinfunction "MDC_31") (pintype "input"))
      (node (ref "D8") (pin "16") (pinfunction "PC1_16") (pintype "bidirectional"))
    )
    (net (code "12") (name "/E_MDIO") (class "Default")
      (node (ref "D10") (pin "30") (pinfunction "MDIO_30") (pintype "bidirectional"))
      (node (ref "D8") (pin "25") (pinfunction "PA2_25") (pintype "bidirectional"))
      (node (ref "R45") (pin "1") (pinfunction "1_1") (pintype "passive"))
    )
    (net (code "13") (name "/E_NRST") (class "Default")
      (node (ref "D10") (pin "29") (pinfunction "RESET_29") (pintype "input"))
      (node (ref "D8") (pin "47") (pinfunction "PB10_47") (pintype "bidirectional"))
    )
    (net (code "14") (name "/E_RMII_CRSDV") (class "Default")
      (node (ref "D10") (pin "40") (pinfunction "CRS/CRS_DV/LED_CFG_40") (pintype "output"))
      (node (ref "D8") (pin "32") (pinfunction "PA7_32") (pintype "bidirectional"))
      (node (ref "R49") (pin "1") (pinfunction "1_1") (pintype "passive"))
    )
    (net (code "15") (name "/E_RXD0") (class "Default")
      (node (ref "D10") (pin "43") (pinfunction "RXD_0/PHYAD1_43") (pintype "output"))
      (node (ref "D8") (pin "33") (pinfunction "PC4_33") (pintype "bidirectional"))
    )
    (net (code "16") (name "/E_RXD1") (class "Default")
      (node (ref "D10") (pin "44") (pinfunction "RXD_1/PHYAD2_44") (pintype "output"))
      (node (ref "D8") (pin "34") (pinfunction "PC5_34") (pintype "bidirectional"))
    )
    (net (code "17") (name "/E_TXD0") (class "Default")
      (node (ref "D10") (pin "3") (pinfunction "TXD_0_3") (pintype "input"))
      (node (ref "D8") (pin "51") (pinfunction "PB12_51") (pintype "bidirectional"))
    )
    (net (code "18") (name "/E_TXD1") (class "Default")
      (node (ref "D10") (pin "4") (pinfunction "TXD_1_4") (pintype "input"))
      (node (ref "D8") (pin "52") (pinfunction "PB13_52") (pintype "bidirectional"))
    )
    (net (code "19") (name "/E_TXEN") (class "Default")
      (node (ref "D10") (pin "2") (pinfunction "TX_EN_2") (pintype "input"))
      (node (ref "D8") (pin "48") (pinfunction "PB11_48") (pintype "bidirectional"))
    )
    (net (code "20") (name "/FL_CSS") (class "Default")
      (node (ref "D1") (pin "4") (pinfunction "CS_4") (pintype "power_in"))
      (node (ref "D8") (pin "35") (pinfunction "PB0_35") (pintype "bidirectional"))
      (node (ref "R2") (pin "1") (pinfunction "1_1") (pintype "passive"))
    )
    (net (code "21") (name "/I2C1_SCL") (class "Default")
      (node (ref "D8") (pin "95") (pinfunction "PB8_95") (pintype "bidirectional"))
      (node (ref "R67") (pin "1") (pinfunction "1_1") (pintype "passive"))
      (node (ref "X11") (pin "4") (pinfunction "4_4") (pintype "passive"))
    )
    (net (code "22") (name "/I2C1_SDA") (class "Default")
      (node (ref "D8") (pin "96") (pinfunction "PB9_96") (pintype "bidirectional"))
      (node (ref "R60") (pin "1") (pinfunction "1_1") (pintype "passive"))
      (node (ref "X11") (pin "5") (pinfunction "5_5") (pintype "passive"))
    )
    (net (code "23") (name "/JDTI") (class "Default")
      (node (ref "D8") (pin "77") (pinfunction "PA15(JTDI)_77") (pintype "bidirectional"))
      (node (ref "R37") (pin "1") (pinfunction "1_1") (pintype "passive"))
      (node (ref "X9") (pin "7") (pinfunction "7_7") (pintype "passive"))
    )
    (net (code "24") (name "/LED1") (class "Default")
      (node (ref "D8") (pin "3") (pinfunction "PE4_3") (pintype "bidirectional"))
      (node (ref "HL6") (pin "2") (pinfunction "K_2") (pintype "passive"))
    )
    (net (code "25") (name "/LED2") (class "Default")
      (node (ref "D8") (pin "2") (pinfunction "PE3_2") (pintype "bidirectional"))
      (node (ref "HL5") (pin "2") (pinfunction "K_2") (pintype "passive"))
    )
    (net (code "26") (name "/LED3") (class "Default")
      (node (ref "D8") (pin "4") (pinfunction "PE5_4") (pintype "bidirectional"))
      (node (ref "HL4") (pin "2") (pinfunction "K_2") (pintype "passive"))
    )
    (net (code "27") (name "/LED_ACT") (class "Default")
      (node (ref "D10") (pin "26") (pinfunction "LED_ACT/COL/AN_EN_26") (pintype "output"))
      (node (ref "R48") (pin "1") (pinfunction "1_1") (pintype "passive"))
      (node (ref "X12") (pin "11") (pinfunction "RC_11") (pintype "passive"))
    )
    (net (code "28") (name "/LED_LINK") (class "Default")
      (node (ref "D10") (pin "28") (pinfunction "LED_LINK/AN0_28") (pintype "output"))
      (node (ref "R50") (pin "1") (pinfunction "1_1") (pintype "passive"))
      (node (ref "X12") (pin "10") (pinfunction "LC_10") (pintype "passive"))
    )
    (net (code "29") (name "/MISO") (class "Default")
      (node (ref "D1") (pin "8") (pinfunction "SO_8") (pintype "power_in"))
      (node (ref "D2") (pin "2") (pinfunction "Q_2") (pintype "passive"))
      (node (ref "D8") (pin "31") (pinfunction "PA6_31") (pintype "bidirectional"))
      (node (ref "X11") (pin "10") (pinfunction "10_10") (pintype "passive"))
    )
    (net (code "30") (name "/MOSI") (class "Default")
      (node (ref "D1") (pin "1") (pinfunction "SI_1") (pintype "passive"))
      (node (ref "D2") (pin "5") (pinfunction "D_5") (pintype "passive"))
      (node (ref "D8") (pin "91") (pinfunction "PB5_91") (pintype "bidirectional"))
      (node (ref "X11") (pin "7") (pinfunction "7_7") (pintype "passive"))
    )
    (net (code "31") (name "/NJRST") (class "Default")
      (node (ref "D8") (pin "90") (pinfunction "PB4(NJTRST)_90") (pintype "bidirectional"))
      (node (ref "R36") (pin "1") (pinfunction "1_1") (pintype "passive"))
      (node (ref "X9") (pin "5") (pinfunction "5_5") (pintype "passive"))
    )
    (net (code "32") (name "/NRST") (class "Default")
      (node (ref "C36") (pin "1") (pinfunction "1_1") (pintype "passive"))
      (node (ref "D8") (pin "14") (pinfunction "NRST_14") (pintype "bidirectional"))
      (node (ref "R31") (pin "1") (pinfunction "1_1") (pintype "passive"))
      (node (ref "S1") (pin "1") (pinfunction "1_1") (pintype "passive"))
    )
    (net (code "33") (name "/PD3") (class "Default")
      (node (ref "D8") (pin "84") (pinfunction "PD3_84") (pintype "bidirectional"))
      (node (ref "X11") (pin "1") (pinfunction "1_1") (pintype "passive"))
    )
    (net (code "34") (name "/PD4") (class "Default")
      (node (ref "D8") (pin "85") (pinfunction "PD4_85") (pintype "bidirectional"))
      (node (ref "X11") (pin "2") (pinfunction "2_2") (pintype "passive"))
    )
    (net (code "35") (name "/PD7") (class "Default")
      (node (ref "D8") (pin "88") (pinfunction "PD7_88") (pintype "bidirectional"))
      (node (ref "X11") (pin "3") (pinfunction "3_3") (pintype "passive"))
    )
    (net (code "36") (name "/PE0") (class "Default")
      (node (ref "D8") (pin "97") (pinfunction "PE0_97") (pintype "bidirectional"))
      (node (ref "X11") (pin "6") (pinfunction "6_6") (pintype "passive"))
    )
    (net (code "37") (name "/PFB") (class "Default")
      (node (ref "C46") (pin "1") (pinfunction "1_1") (pintype "passive"))
      (node (ref "C47") (pin "1") (pinfunction "1_1") (pintype "passive"))
      (node (ref "C52") (pin "1") (pinfunction "1_1") (pintype "passive"))
      (node (ref "C54") (pin "1") (pinfunction "1_1") (pintype "passive"))
      (node (ref "D10") (pin "18") (pinfunction "PFBIN1_18") (pintype "input"))
      (node (ref "D10") (pin "23") (pinfunction "PFBOUT_23") (pintype "output"))
      (node (ref "D10") (pin "37") (pinfunction "PFBIN2_37") (pintype "input"))
    )
    (net (code "38") (name "/RD_N") (class "Default")
      (node (ref "D10") (pin "13") (pinfunction "RD-_13") (pintype "bidirectional"))
      (node (ref "R65") (pin "1") (pinfunction "1_1") (pintype "passive"))
      (node (ref "VD8") (pin "5") (pinfunction "D_5") (pintype "passive"))
      (node (ref "X12") (pin "6") (pinfunction "RD-_6") (pintype "passive"))
    )
    (net (code "39") (name "/RD_P") (class "Default")
      (node (ref "D10") (pin "14") (pinfunction "RD+_14") (pintype "bidirectional"))
      (node (ref "R63") (pin "1") (pinfunction "1_1") (pintype "passive"))
      (node (ref "VD8") (pin "4") (pinfunction "B_4") (pintype "passive"))
      (node (ref "X12") (pin "3") (pinfunction "RD+_3") (pintype "passive"))
    )
    (net (code "40") (name "/RS485_Cntr") (class "Default")
      (node (ref "D6") (pin "2") (pinfunction "RE_2") (pintype "passive"))
      (node (ref "D6") (pin "3") (pinfunction "DE_3") (pintype "passive"))
      (node (ref "D8") (pin "1") (pinfunction "PE2_1") (pintype "bidirectional"))
      (node (ref "R11") (pin "2") (pinfunction "2_2") (pintype "passive"))
    )
    (net (code "41") (name "/RS485_N") (class "Default")
      (node (ref "D6") (pin "6") (pinfunction "A_6") (pintype "passive"))
      (node (ref "R22") (pin "2") (pinfunction "2_2") (pintype "passive"))
      (node (ref "X6") (pin "2") (pinfunction "2_2") (pintype "passive"))
      (node (ref "X7") (pin "4") (pinfunction "4_4") (pintype "passive"))
    )
    (net (code "42") (name "/RS485_P") (class "Default")
      (node (ref "D6") (pin "7") (pinfunction "B_7") (pintype "passive"))
      (node (ref "D9") (pin "13") (pinfunction "R1IN_13") (pintype "passive"))
      (node (ref "R20") (pin "1") (pinfunction "1_1") (pintype "passive"))
      (node (ref "R21") (pin "2") (pinfunction "2_2") (pintype "passive"))
      (node (ref "X7") (pin "3") (pinfunction "3_3") (pintype "passive"))
    )
    (net (code "43") (name "/RX2") (class "Default")
      (node (ref "D6") (pin "1") (pinfunction "RO_1") (pintype "passive"))
      (node (ref "D8") (pin "87") (pinfunction "PD6_87") (pintype "bidirectional"))
      (node (ref "D9") (pin "12") (pinfunction "R1OUT_12") (pintype "passive"))
      (node (ref "R10") (pin "1") (pinfunction "1_1") (pintype "passive"))
    )
    (net (code "44") (name "/SCK") (class "Default")
      (node (ref "D1") (pin "2") (pinfunction "SCK_2") (pintype "passive"))
      (node (ref "D2") (pin "6") (pinfunction "C_6") (pintype "passive"))
      (node (ref "D8") (pin "30") (pinfunction "PA5_30") (pintype "bidirectional"))
      (node (ref "R5") (pin "2") (pinfunction "2_2") (pintype "passive"))
      (node (ref "X11") (pin "9") (pinfunction "9_9") (pintype "passive"))
    )
    (net (code "45") (name "/SDIO_CLK") (class "Default")
      (node (ref "D8") (pin "80") (pinfunction "PC12_80") (pintype "bidirectional"))
      (node (ref "R18") (pin "1") (pinfunction "1_1") (pintype "passive"))
      (node (ref "X4") (pin "5") (pinfunction "CLK_5") (pintype "passive"))
    )
    (net (code "46") (name "/SDIO_CMD") (class "Default")
      (node (ref "D8") (pin "83") (pinfunction "PD2_83") (pintype "bidirectional"))
      (node (ref "R17") (pin "1") (pinfunction "1_1") (pintype "passive"))
      (node (ref "X4") (pin "3") (pinfunction "CMD_3") (pintype "passive"))
    )
    (net (code "47") (name "/SDIO_D0") (class "Default")
      (node (ref "D8") (pin "65") (pinfunction "PC8_65") (pintype "bidirectional"))
      (node (ref "R12") (pin "1") (pinfunction "1_1") (pintype "passive"))
      (node (ref "X4") (pin "7") (pinfunction "D0_7") (pintype "passive"))
    )
    (net (code "48") (name "/SDIO_D1") (class "Default")
      (node (ref "D8") (pin "66") (pinfunction "PC9_66") (pintype "bidirectional"))
      (node (ref "R13") (pin "1") (pinfunction "1_1") (pintype "passive"))
      (node (ref "X4") (pin "8") (pinfunction "D1_8") (pintype "passive"))
    )
    (net (code "49") (name "/SDIO_D2") (class "Default")
      (node (ref "D8") (pin "78") (pinfunction "PC10_78") (pintype "bidirectional"))
      (node (ref "R14") (pin "1") (pinfunction "1_1") (pintype "passive"))
      (node (ref "X4") (pin "1") (pinfunction "D2_1") (pintype "passive"))
    )
    (net (code "50") (name "/SDIO_D3") (class "Default")
      (node (ref "D8") (pin "79") (pinfunction "PC11_79") (pintype "bidirectional"))
      (node (ref "R15") (pin "1") (pinfunction "1_1") (pintype "passive"))
      (node (ref "X4") (pin "2") (pinfunction "D3_2") (pintype "passive"))
    )
    (net (code "51") (name "/SWCLK") (class "Default")
      (node (ref "D8") (pin "76") (pinfunction "PA14(JTCK-SWCLK)_76") (pintype "bidirectional"))
      (node (ref "R41") (pin "2") (pinfunction "2_2") (pintype "passive"))
      (node (ref "X9") (pin "4") (pinfunction "4_4") (pintype "passive"))
    )
    (net (code "52") (name "/SWDIO") (class "Default")
      (node (ref "D8") (pin "72") (pinfunction "PA13(JTMS-SWDIO)_72") (pintype "bidirectional"))
      (node (ref "R38") (pin "1") (pinfunction "1_1") (pintype "passive"))
      (node (ref "X9") (pin "2") (pinfunction "2_2") (pintype "passive"))
    )
    (net (code "53") (name "/SWITCH1") (class "Default")
      (node (ref "D8") (pin "64") (pinfunction "PC7_64") (pintype "bidirectional"))
      (node (ref "R54") (pin "1") (pinfunction "1_1") (pintype "passive"))
      (node (ref "S2") (pin "1") (pinfunction "1_1") (pintype "passive"))
    )
    (net (code "54") (name "/SWITCH2") (class "Default")
      (node (ref "D8") (pin "63") (pinfunction "PC6_63") (pintype "bidirectional"))
      (node (ref "R55") (pin "1") (pinfunction "1_1") (pintype "passive"))
      (node (ref "S2") (pin "2") (pinfunction "2_2") (pintype "passive"))
    )
    (net (code "55") (name "/SWITCH3") (class "Default")
      (node (ref "D8") (pin "62") (pinfunction "PD15_62") (pintype "bidirectional"))
      (node (ref "R56") (pin "1") (pinfunction "1_1") (pintype "passive"))
      (node (ref "S2") (pin "3") (pinfunction "3_3") (pintype "passive"))
    )
    (net (code "56") (name "/SWITCH4") (class "Default")
      (node (ref "D8") (pin "61") (pinfunction "PD14_61") (pintype "bidirectional"))
      (node (ref "R57") (pin "1") (pinfunction "1_1") (pintype "passive"))
      (node (ref "S2") (pin "4") (pinfunction "4_4") (pintype "passive"))
    )
    (net (code "57") (name "/SWITCH5") (class "Default")
      (node (ref "D8") (pin "60") (pinfunction "PD13_60") (pintype "bidirectional"))
      (node (ref "R59") (pin "1") (pinfunction "1_1") (pintype "passive"))
      (node (ref "S2") (pin "5") (pinfunction "5_5") (pintype "passive"))
    )
    (net (code "58") (name "/SWITCH6") (class "Default")
      (node (ref "D8") (pin "59") (pinfunction "PD12_59") (pintype "bidirectional"))
      (node (ref "R62") (pin "1") (pinfunction "1_1") (pintype "passive"))
      (node (ref "S2") (pin "6") (pinfunction "6_6") (pintype "passive"))
    )
    (net (code "59") (name "/SWITCH7") (class "Default")
      (node (ref "D8") (pin "58") (pinfunction "PD11_58") (pintype "bidirectional"))
      (node (ref "R64") (pin "1") (pinfunction "1_1") (pintype "passive"))
      (node (ref "S2") (pin "7") (pinfunction "7_7") (pintype "passive"))
    )
    (net (code "60") (name "/SWITCH8") (class "Default")
      (node (ref "D8") (pin "57") (pinfunction "PD10_57") (pintype "bidirectional"))
      (node (ref "R66") (pin "1") (pinfunction "1_1") (pintype "passive"))
      (node (ref "S2") (pin "8") (pinfunction "8_8") (pintype "passive"))
    )
    (net (code "61") (name "/SWO") (class "Default")
      (node (ref "D8") (pin "89") (pinfunction "PB3(JTDO/TRACESWO)_89") (pintype "bidirectional"))
      (node (ref "R40") (pin "1") (pinfunction "1_1") (pintype "passive"))
      (node (ref "X9") (pin "6") (pinfunction "6_6") (pintype "passive"))
    )
    (net (code "62") (name "/TD_N") (class "Default")
      (node (ref "D10") (pin "16") (pinfunction "TD-_16") (pintype "bidirectional"))
      (node (ref "R61") (pin "1") (pinfunction "1_1") (pintype "passive"))
      (node (ref "VD8") (pin "3") (pinfunction "C_3") (pintype "passive"))
      (node (ref "X12") (pin "2") (pinfunction "TD-_2") (pintype "passive"))
    )
    (net (code "63") (name "/TD_P") (class "Default")
      (node (ref "D10") (pin "17") (pinfunction "TD+_17") (pintype "bidirectional"))
      (node (ref "R58") (pin "1") (pinfunction "1_1") (pintype "passive"))
      (node (ref "VD8") (pin "1") (pinfunction "A_1") (pintype "passive"))
      (node (ref "X12") (pin "1") (pinfunction "TD+_1") (pintype "passive"))
    )
    (net (code "64") (name "/TX2") (class "Default")
      (node (ref "D6") (pin "4") (pinfunction "DI_4") (pintype "power_in"))
      (node (ref "D8") (pin "86") (pinfunction "PD5_86") (pintype "bidirectional"))
      (node (ref "D9") (pin "11") (pinfunction "T1IN_11") (pintype "passive"))
    )
    (net (code "65") (name "/TxD") (class "Default")
      (node (ref "D9") (pin "14") (pinfunction "T1OUT_14") (pintype "passive"))
      (node (ref "X7") (pin "2") (pinfunction "2_2") (pintype "passive"))
    )
    (net (code "66") (name "/USART1_Rx") (class "Default")
      (node (ref "D4") (pin "1") (pinfunction "TXD_1") (pintype "output"))
      (node (ref "D8") (pin "69") (pinfunction "PA10_69") (pintype "bidirectional"))
      (node (ref "R16") (pin "1") (pinfunction "1_1") (pintype "passive"))
    )
    (net (code "67") (name "/USART1_Tx") (class "Default")
      (node (ref "D4") (pin "4") (pinfunction "RXD_4") (pintype "input"))
      (node (ref "D8") (pin "68") (pinfunction "PA9_68") (pintype "bidirectional"))
      (node (ref "R19") (pin "1") (pinfunction "1_1") (pintype "passive"))
    )
    (net (code "68") (name "/USART3_Rx") (class "Default")
      (node (ref "D8") (pin "56") (pinfunction "PD9_56") (pintype "bidirectional"))
      (node (ref "X10") (pin "3") (pinfunction "3_3") (pintype "passive"))
    )
    (net (code "69") (name "/USART3_Tx") (class "Default")
      (node (ref "D8") (pin "55") (pinfunction "PD8_55") (pintype "bidirectional"))
      (node (ref "X10") (pin "2") (pinfunction "2_2") (pintype "passive"))
    )
    (net (code "70") (name "/USB_N") (class "Default")
      (node (ref "C5") (pin "2") (pinfunction "2_2") (pintype "passive"))
      (node (ref "D4") (pin "9") (pinfunction "USBDM_9") (pintype "input"))
      (node (ref "R7") (pin "1") (pinfunction "1_1") (pintype "passive"))
      (node (ref "R7") (pin "2") (pinfunction "2_2") (pintype "passive"))
      (node (ref "VD2") (pin "3") (pinfunction "B_3") (pintype "passive"))
      (node (ref "X1") (pin "2") (pinfunction "D-_2") (pintype "passive"))
    )
    (net (code "71") (name "/USB_P") (class "Default")
      (node (ref "C4") (pin "2") (pinfunction "2_2") (pintype "passive"))
      (node (ref "D4") (pin "8") (pinfunction "USBDP_8") (pintype "input"))
      (node (ref "R6") (pin "1") (pinfunction "1_1") (pintype "passive"))
      (node (ref "R6") (pin "2") (pinfunction "2_2") (pintype "passive"))
      (node (ref "VD2") (pin "4") (pinfunction "C_4") (pintype "passive"))
      (node (ref "X1") (pin "3") (pinfunction "D+_3") (pintype "passive"))
    )
    (net (code "72") (name "/nHOLD") (class "Default")
      (node (ref "D2") (pin "7") (pinfunction "HOLD_7") (pintype "passive"))
      (node (ref "D8") (pin "29") (pinfunction "PA4_29") (pintype "bidirectional"))
    )
    (net (code "73") (name "/nW") (class "Default")
      (node (ref "D2") (pin "3") (pinfunction "W_3") (pintype "passive"))
      (node (ref "D8") (pin "38") (pinfunction "PE7_38") (pintype "bidirectional"))
    )
    (net (code "74") (name "3V3") (class "Default")
      (node (ref "BQ3") (pin "4") (pinfunction "+VS_4") (pintype "passive"))
      (node (ref "C10") (pin "1") (pinfunction "1_1") (pintype "passive"))
      (node (ref "C11") (pin "1") (pinfunction "1_1") (pintype "passive"))
      (node (ref "C19") (pin "1") (pinfunction "1_1") (pintype "passive"))
      (node (ref "C2") (pin "2") (pinfunction "2_2") (pintype "passive"))
      (node (ref "C20") (pin "2") (pinfunction "2_2") (pintype "passive"))
      (node (ref "C21") (pin "2") (pinfunction "2_2") (pintype "passive"))
      (node (ref "C22") (pin "2") (pinfunction "2_2") (pintype "passive"))
      (node (ref "C23") (pin "1") (pinfunction "1_1") (pintype "passive"))
      (node (ref "C24") (pin "2") (pinfunction "2_2") (pintype "passive"))
      (node (ref "C27") (pin "2") (pinfunction "2_2") (pintype "passive"))
      (node (ref "C28") (pin "2") (pinfunction "2_2") (pintype "passive"))
      (node (ref "C3") (pin "1") (pinfunction "1_1") (pintype "passive"))
      (node (ref "C33") (pin "2") (pinfunction "2_2") (pintype "passive"))
      (node (ref "C39") (pin "1") (pinfunction "1_1") (pintype "passive"))
      (node (ref "C40") (pin "1") (pinfunction "1_1") (pintype "passive"))
      (node (ref "C41") (pin "1") (pinfunction "1_1") (pintype "passive"))
      (node (ref "C42") (pin "1") (pinfunction "1_1") (pintype "passive"))
      (node (ref "C43") (pin "2") (pinfunction "2_2") (pintype "passive"))
      (node (ref "C45") (pin "2") (pinfunction "2_2") (pintype "passive"))
      (node (ref "C48") (pin "2") (pinfunction "2_2") (pintype "passive"))
      (node (ref "C49") (pin "2") (pinfunction "2_2") (pintype "passive"))
      (node (ref "C50") (pin "1") (pinfunction "1_1") (pintype "passive"))
      (node (ref "C51") (pin "1") (pinfunction "1_1") (pintype "passive"))
      (node (ref "C8") (pin "2") (pinfunction "2_2") (pintype "passive"))
      (node (ref "D1") (pin "3") (pinfunction "RESET_3") (pintype "passive"))
      (node (ref "D1") (pin "5") (pinfunction "WP_5") (pintype "passive"))
      (node (ref "D1") (pin "6") (pinfunction "VCC_6") (pintype "passive"))
      (node (ref "D10") (pin "22") (pinfunction "AVDD33_22") (pintype "power_in"))
      (node (ref "D10") (pin "32") (pinfunction "IOVDD33_2_32") (pintype "power_in"))
      (node (ref "D10") (pin "48") (pinfunction "IOVDD33_48") (pintype "power_in"))
      (node (ref "D2") (pin "8") (pinfunction "VCC_8") (pintype "power_in"))
      (node (ref "D3") (pin "3") (pinfunction "VCC_3") (pintype "power_in"))
      (node (ref "D6") (pin "8") (pinfunction "VCC_8") (pintype "power_in"))
      (node (ref "D7") (pin "2") (pinfunction "UOUT_2") (pintype "output"))
      (node (ref "D8") (pin "100") (pinfunction "VDD_100") (pintype "power_in"))
      (node (ref "D8") (pin "11") (pinfunction "VDD_11") (pintype "power_in"))
      (node (ref "D8") (pin "19") (pinfunction "VDD_19") (pintype "power_in"))
      (node (ref "D8") (pin "28") (pinfunction "VDD_28") (pintype "power_in"))
      (node (ref "D8") (pin "50") (pinfunction "VDD_50") (pintype "power_in"))
      (node (ref "D8") (pin "75") (pinfunction "VDD_75") (pintype "power_in"))
      (node (ref "D9") (pin "16") (pinfunction "VCC_16") (pintype "power_in"))
      (node (ref "L2") (pin "1") (pinfunction "1_1") (pintype "passive"))
      (node (ref "R1") (pin "2") (pinfunction "2_2") (pintype "passive"))
      (node (ref "R10") (pin "2") (pinfunction "2_2") (pintype "passive"))
      (node (ref "R12") (pin "2") (pinfunction "2_2") (pintype "passive"))
      (node (ref "R13") (pin "2") (pinfunction "2_2") (pintype "passive"))
      (node (ref "R14") (pin "2") (pinfunction "2_2") (pintype "passive"))
      (node (ref "R15") (pin "2") (pinfunction "2_2") (pintype "passive"))
      (node (ref "R17") (pin "2") (pinfunction "2_2") (pintype "passive"))
      (node (ref "R18") (pin "2") (pinfunction "2_2") (pintype "passive"))
      (node (ref "R2") (pin "2") (pinfunction "2_2") (pintype "passive"))
      (node (ref "R22") (pin "1") (pinfunction "1_1") (pintype "passive"))
      (node (ref "R31") (pin "2") (pinfunction "2_2") (pintype "passive"))
      (node (ref "R32") (pin "1") (pinfunction "1_1") (pintype "passive"))
      (node (ref "R33") (pin "1") (pinfunction "1_1") (pintype "passive"))
      (node (ref "R34") (pin "1") (pinfunction "1_1") (pintype "passive"))
      (node (ref "R35") (pin "2") (pinfunction "2_2") (pintype "passive"))
      (node (ref "R36") (pin "2") (pinfunction "2_2") (pintype "passive"))
      (node (ref "R37") (pin "2") (pinfunction "2_2") (pintype "passive"))
      (node (ref "R38") (pin "2") (pinfunction "2_2") (pintype "passive"))
      (node (ref "R40") (pin "2") (pinfunction "2_2") (pintype "passive"))
      (node (ref "R42") (pin "2") (pinfunction "2_2") (pintype "passive"))
      (node (ref "R43") (pin "2") (pinfunction "2_2") (pintype "passive"))
      (node (ref "R45") (pin "2") (pinfunction "2_2") (pintype "passive"))
      (node (ref "R46") (pin "2") (pinfunction "2_2") (pintype "passive"))
      (node (ref "R47") (pin "2") (pinfunction "2_2") (pintype "passive"))
      (node (ref "R48") (pin "2") (pinfunction "2_2") (pintype "passive"))
      (node (ref "R49") (pin "2") (pinfunction "2_2") (pintype "passive"))
      (node (ref "R50") (pin "2") (pinfunction "2_2") (pintype "passive"))
      (node (ref "R52") (pin "2") (pinfunction "2_2") (pintype "passive"))
      (node (ref "R54") (pin "2") (pinfunction "2_2") (pintype "passive"))
      (node (ref "R55") (pin "2") (pinfunction "2_2") (pintype "passive"))
      (node (ref "R56") (pin "2") (pinfunction "2_2") (pintype "passive"))
      (node (ref "R57") (pin "2") (pinfunction "2_2") (pintype "passive"))
      (node (ref "R58") (pin "2") (pinfunction "2_2") (pintype "passive"))
      (node (ref "R59") (pin "2") (pinfunction "2_2") (pintype "passive"))
      (node (ref "R60") (pin "2") (pinfunction "2_2") (pintype "passive"))
      (node (ref "R61") (pin "2") (pinfunction "2_2") (pintype "passive"))
      (node (ref "R62") (pin "2") (pinfunction "2_2") (pintype "passive"))
      (node (ref "R63") (pin "2") (pinfunction "2_2") (pintype "passive"))
      (node (ref "R64") (pin "2") (pinfunction "2_2") (pintype "passive"))
      (node (ref "R65") (pin "2") (pinfunction "2_2") (pintype "passive"))
      (node (ref "R66") (pin "2") (pinfunction "2_2") (pintype "passive"))
      (node (ref "R67") (pin "2") (pinfunction "2_2") (pintype "passive"))
      (node (ref "R69") (pin "2") (pinfunction "2_2") (pintype "passive"))
      (node (ref "R70") (pin "2") (pinfunction "2_2") (pintype "passive"))
      (node (ref "VD7") (pin "2") (pinfunction "A2_2") (pintype "passive"))
      (node (ref "X11") (pin "11") (pinfunction "11_11") (pintype "passive"))
      (node (ref "X11") (pin "12") (pinfunction "12_12") (pintype "passive"))
      (node (ref "X12") (pin "4") (pinfunction "CTT_4") (pintype "passive"))
      (node (ref "X12") (pin "5") (pinfunction "CTR_5") (pintype "passive"))
      (node (ref "X4") (pin "4") (pinfunction "3V3_4") (pintype "passive"))
      (node (ref "X5") (pin "1") (pinfunction "1_1") (pintype "passive"))
      (node (ref "X7") (pin "1") (pinfunction "1_1") (pintype "passive"))
      (node (ref "X8") (pin "1") (pinfunction "1_1") (pintype "passive"))
      (node (ref "X8") (pin "2") (pinfunction "2_2") (pintype "passive"))
      (node (ref "X9") (pin "1") (pinfunction "1_1") (pintype "passive"))
      (node (ref "X9") (pin "3") (pinfunction "3_3") (pintype "passive"))
    )
    (net (code "75") (name "5V") (class "Default")
      (node (ref "C12") (pin "2") (pinfunction "2_2") (pintype "passive"))
      (node (ref "C13") (pin "1") (pinfunction "+_1") (pintype "passive"))
      (node (ref "C14") (pin "2") (pinfunction "2_2") (pintype "passive"))
      (node (ref "C44") (pin "2") (pinfunction "2_2") (pintype "passive"))
      (node (ref "D7") (pin "3") (pinfunction "VIN_3") (pintype "bidirectional"))
      (node (ref "G1") (pin "+") (pinfunction "+_+") (pintype "passive"))
      (node (ref "L1") (pin "2") (pinfunction "2_2") (pintype "passive"))
      (node (ref "R26") (pin "2") (pinfunction "2_2") (pintype "passive"))
      (node (ref "VD4") (pin "C") (pinfunction "C_C") (pintype "passive"))
      (node (ref "X10") (pin "4") (pinfunction "4_4") (pintype "passive"))
      (node (ref "X11") (pin "13") (pinfunction "13_13") (pintype "passive"))
      (node (ref "X11") (pin "14") (pinfunction "14_14") (pintype "passive"))
      (node (ref "X5") (pin "9") (pinfunction "9_9") (pintype "passive"))
      (node (ref "X7") (pin "9") (pinfunction "9_9") (pintype "passive"))
    )
    (net (code "76") (name "GND") (class "Default")
      (node (ref "BQ3") (pin "2") (pinfunction "GND_2") (pintype "passive"))
      (node (ref "C1") (pin "1") (pinfunction "1_1") (pintype "passive"))
      (node (ref "C10") (pin "2") (pinfunction "2_2") (pintype "passive"))
      (node (ref "C11") (pin "2") (pinfunction "2_2") (pintype "passive"))
      (node (ref "C12") (pin "1") (pinfunction "1_1") (pintype "passive"))
      (node (ref "C13") (pin "2") (pinfunction "-_2") (pintype "passive"))
      (node (ref "C14") (pin "1") (pinfunction "1_1") (pintype "passive"))
      (node (ref "C15") (pin "2") (pinfunction "2_2") (pintype "passive"))
      (node (ref "C16") (pin "2") (pinfunction "2_2") (pintype "passive"))
      (node (ref "C19") (pin "2") (pinfunction "2_2") (pintype "passive"))
      (node (ref "C2") (pin "1") (pinfunction "1_1") (pintype "passive"))
      (node (ref "C21") (pin "1") (pinfunction "1_1") (pintype "passive"))
      (node (ref "C22") (pin "1") (pinfunction "1_1") (pintype "passive"))
      (node (ref "C23") (pin "2") (pinfunction "2_2") (pintype "passive"))
      (node (ref "C24") (pin "1") (pinfunction "1_1") (pintype "passive"))
      (node (ref "C25") (pin "2") (pinfunction "2_2") (pintype "passive"))
      (node (ref "C26") (pin "2") (pinfunction "2_2") (pintype "passive"))
      (node (ref "C27") (pin "1") (pinfunction "1_1") (pintype "passive"))
      (node (ref "C28") (pin "1") (pinfunction "1_1") (pintype "passive"))
      (node (ref "C29") (pin "1") (pinfunction "1_1") (pintype "passive"))
      (node (ref "C3") (pin "2") (pinfunction "2_2") (pintype "passive"))
      (node (ref "C30") (pin "2") (pinfunction "2_2") (pintype "passive"))
      (node (ref "C31") (pin "1") (pinfunction "1_1") (pintype "passive"))
      (node (ref "C32") (pin "1") (pinfunction "1_1") (pintype "passive"))
      (node (ref "C33") (pin "1") (pinfunction "1_1") (pintype "passive"))
      (node (ref "C34") (pin "1") (pinfunction "1_1") (pintype "passive"))
      (node (ref "C35") (pin "1") (pinfunction "1_1") (pintype "passive"))
      (node (ref "C36") (pin "2") (pinfunction "2_2") (pintype "passive"))
      (node (ref "C37") (pin "1") (pinfunction "1_1") (pintype "passive"))
      (node (ref "C38") (pin "2") (pinfunction "2_2") (pintype "passive"))
      (node (ref "C39") (pin "2") (pinfunction "2_2") (pintype "passive"))
      (node (ref "C4") (pin "1") (pinfunction "1_1") (pintype "passive"))
      (node (ref "C40") (pin "2") (pinfunction "2_2") (pintype "passive"))
      (node (ref "C41") (pin "2") (pinfunction "2_2") (pintype "passive"))
      (node (ref "C42") (pin "2") (pinfunction "2_2") (pintype "passive"))
      (node (ref "C43") (pin "1") (pinfunction "1_1") (pintype "passive"))
      (node (ref "C44") (pin "1") (pinfunction "1_1") (pintype "passive"))
      (node (ref "C45") (pin "1") (pinfunction "1_1") (pintype "passive"))
      (node (ref "C46") (pin "2") (pinfunction "2_2") (pintype "passive"))
      (node (ref "C47") (pin "2") (pinfunction "2_2") (pintype "passive"))
      (node (ref "C48") (pin "1") (pinfunction "1_1") (pintype "passive"))
      (node (ref "C49") (pin "1") (pinfunction "1_1") (pintype "passive"))
      (node (ref "C5") (pin "1") (pinfunction "1_1") (pintype "passive"))
      (node (ref "C50") (pin "2") (pinfunction "2_2") (pintype "passive"))
      (node (ref "C51") (pin "2") (pinfunction "2_2") (pintype "passive"))
      (node (ref "C52") (pin "2") (pinfunction "2_2") (pintype "passive"))
      (node (ref "C53") (pin "1") (pinfunction "1_1") (pintype "passive"))
      (node (ref "C54") (pin "2") (pinfunction "2_2") (pintype "passive"))
      (node (ref "C6") (pin "1") (pinfunction "1_1") (pintype "passive"))
      (node (ref "C7") (pin "2") (pinfunction "-_2") (pintype "passive"))
      (node (ref "C8") (pin "1") (pinfunction "1_1") (pintype "passive"))
      (node (ref "C9") (pin "1") (pinfunction "1_1") (pintype "passive"))
      (node (ref "D1") (pin "7") (pinfunction "GND_7") (pintype "passive"))
      (node (ref "D10") (pin "15") (pinfunction "AGND_2_15") (pintype "passive"))
      (node (ref "D10") (pin "19") (pinfunction "AGND_19") (pintype "passive"))
      (node (ref "D10") (pin "35") (pinfunction "IOGND_2_35") (pintype "passive"))
      (node (ref "D10") (pin "36") (pinfunction "DGND_36") (pintype "passive"))
      (node (ref "D10") (pin "47") (pinfunction "IOGND_47") (pintype "passive"))
      (node (ref "D10") (pin "49") (pinfunction "EPAD_49") (pintype "passive"))
      (node (ref "D2") (pin "4") (pinfunction "VSS_4") (pintype "power_in"))
      (node (ref "D3") (pin "2") (pinfunction "GND_2") (pintype "power_in"))
      (node (ref "D4") (pin "13") (pinfunction "GND@1_13") (pintype "power_in"))
      (node (ref "D4") (pin "5") (pinfunction "GND_5") (pintype "power_in"))
      (node (ref "D5") (pin "3") (pinfunction "GND_2_3") (pintype "passive"))
      (node (ref "D5") (pin "5") (pinfunction "~{ON}/OFF_5") (pintype "input"))
      (node (ref "D5") (pin "6") (pinfunction "GND_6") (pintype "passive"))
      (node (ref "D6") (pin "5") (pinfunction "GND_5") (pintype "passive"))
      (node (ref "D7") (pin "1") (pinfunction "GND_1") (pintype "passive"))
      (node (ref "D8") (pin "10") (pinfunction "VSS_10") (pintype "power_in"))
      (node (ref "D8") (pin "20") (pinfunction "VSSA_20") (pintype "power_in"))
      (node (ref "D8") (pin "27") (pinfunction "VSS_27") (pintype "power_in"))
      (node (ref "D8") (pin "74") (pinfunction "VSS_74") (pintype "power_in"))
      (node (ref "D8") (pin "99") (pinfunction "VSS_99") (pintype "power_in"))
      (node (ref "D9") (pin "15") (pinfunction "GND_15") (pintype "passive"))
      (node (ref "HL1") (pin "2") (pinfunction "K_2") (pintype "passive"))
      (node (ref "J1") (pin "3") (pinfunction "NEG_3") (pintype "passive"))
      (node (ref "R11") (pin "1") (pinfunction "1_1") (pintype "passive"))
      (node (ref "R20") (pin "2") (pinfunction "2_2") (pintype "passive"))
      (node (ref "R25") (pin "1") (pinfunction "1_1") (pintype "passive"))
      (node (ref "R41") (pin "1") (pinfunction "1_1") (pintype "passive"))
      (node (ref "R5") (pin "1") (pinfunction "1_1") (pintype "passive"))
      (node (ref "R53") (pin "2") (pinfunction "2_2") (pintype "passive"))
      (node (ref "R68") (pin "1") (pinfunction "1_1") (pintype "passive"))
      (node (ref "S1") (pin "2") (pinfunction "2_2") (pintype "passive"))
      (node (ref "S2") (pin "10") (pinfunction "10_10") (pintype "passive"))
      (node (ref "S2") (pin "11") (pinfunction "11_11") (pintype "passive"))
      (node (ref "S2") (pin "12") (pinfunction "12_12") (pintype "passive"))
      (node (ref "S2") (pin "13") (pinfunction "13_13") (pintype "passive"))
      (node (ref "S2") (pin "14") (pinfunction "14_14") (pintype "passive"))
      (node (ref "S2") (pin "15") (pinfunction "15_15") (pintype "passive"))
      (node (ref "S2") (pin "16") (pinfunction "16_16") (pintype "passive"))
      (node (ref "S2") (pin "9") (pinfunction "9_9") (pintype "passive"))
      (node (ref "VD1") (pin "2") (pinfunction "K_2") (pintype "passive"))
      (node (ref "VD2") (pin "1") (pinfunction "GND_1") (pintype "passive"))
      (node (ref "VD5") (pin "1") (pinfunction "GND_1") (pintype "passive"))
      (node (ref "VD6") (pin "1") (pinfunction "POS_1") (pintype "passive"))
      (node (ref "VD8") (pin "2") (pinfunction "GND_2") (pintype "passive"))
      (node (ref "VT1") (pin "E") (pinfunction "E_E") (pintype "passive"))
      (node (ref "X1") (pin "5") (pinfunction "GND_5") (pintype "passive"))
      (node (ref "X10") (pin "1") (pinfunction "1_1") (pintype "passive"))
      (node (ref "X11") (pin "15") (pinfunction "15_15") (pintype "passive"))
      (node (ref "X11") (pin "16") (pinfunction "16_16") (pintype "passive"))
      (node (ref "X11") (pin "8") (pinfunction "8_8") (pintype "passive"))
      (node (ref "X12") (pin "8") (pinfunction "CG_8") (pintype "passive"))
      (node (ref "X2") (pin "2") (pinfunction "2_2") (pintype "passive"))
      (node (ref "X4") (pin "6") (pinfunction "GND_6") (pintype "passive"))
      (node (ref "X5") (pin "3") (pinfunction "3_3") (pintype "passive"))
      (node (ref "X5") (pin "5") (pinfunction "5_5") (pintype "passive"))
      (node (ref "X7") (pin "5") (pinfunction "5_5") (pintype "passive"))
      (node (ref "X8") (pin "5") (pinfunction "5_5") (pintype "passive"))
      (node (ref "X8") (pin "6") (pinfunction "6_6") (pintype "passive"))
      (node (ref "X9") (pin "8") (pinfunction "8_8") (pintype "passive"))
    )
    (net (code "77") (name "Net-(C7-+)") (class "Default")
      (node (ref "C6") (pin "2") (pinfunction "2_2") (pintype "passive"))
      (node (ref "C7") (pin "1") (pinfunction "+_1") (pintype "passive"))
      (node (ref "D5") (pin "1") (pinfunction "VIN_1") (pintype "power_in"))
      (node (ref "R8") (pin "1") (pinfunction "1_1") (pintype "passive"))
      (node (ref "VD3") (pin "2") (pinfunction "NEG_2") (pintype "passive"))
    )
    (net (code "78") (name "Net-(D3-RS)") (class "Default")
      (node (ref "D3") (pin "8") (pinfunction "RS_8") (pintype "input"))
      (node (ref "R3") (pin "1") (pinfunction "1_1") (pintype "passive"))
    )
    (net (code "79") (name "Net-(D4-CBUS1)") (class "Default")
      (node (ref "D4") (pin "14") (pinfunction "CBUS1_14") (pintype "bidirectional"))
      (node (ref "HL2") (pin "2") (pinfunction "NEG_2") (pintype "passive"))
    )
    (net (code "80") (name "Net-(D4-CBUS2)") (class "Default")
      (node (ref "D4") (pin "7") (pinfunction "CBUS2_7") (pintype "bidirectional"))
      (node (ref "HL3") (pin "2") (pinfunction "NEG_2") (pintype "passive"))
    )
    (net (code "81") (name "Net-(D5-FB)") (class "Default")
      (node (ref "D5") (pin "4") (pinfunction "FB_4") (pintype "input"))
      (node (ref "R25") (pin "2") (pinfunction "2_2") (pintype "passive"))
      (node (ref "R26") (pin "1") (pinfunction "1_1") (pintype "passive"))
    )
    (net (code "82") (name "Net-(D5-OUT)") (class "Default")
      (node (ref "D5") (pin "2") (pinfunction "OUT_2") (pintype "output"))
      (node (ref "L1") (pin "1") (pinfunction "1_1") (pintype "passive"))
      (node (ref "VD6") (pin "2") (pinfunction "NEG_2") (pintype "passive"))
    )
    (net (code "83") (name "Net-(D8A-BOOT0)") (class "Default")
      (node (ref "D8") (pin "94") (pinfunction "BOOT0_94") (pintype "input"))
      (node (ref "R29") (pin "1") (pinfunction "1_1") (pintype "passive"))
    )
    (net (code "84") (name "Net-(D8A-PB2-BOOT1(PB2))") (class "Default")
      (node (ref "D8") (pin "37") (pinfunction "PB2-BOOT1(PB2)_37") (pintype "bidirectional"))
      (node (ref "R28") (pin "1") (pinfunction "1_1") (pintype "passive"))
    )
    (net (code "85") (name "Net-(D8A-PC14-OSC32_IN(PC14))") (class "Default")
      (node (ref "BQ1") (pin "2") (pinfunction "2_2") (pintype "passive"))
      (node (ref "C15") (pin "1") (pinfunction "1_1") (pintype "passive"))
      (node (ref "D8") (pin "8") (pinfunction "PC14-OSC32_IN(PC14)_8") (pintype "bidirectional"))
    )
    (net (code "86") (name "Net-(D8A-PC15-OSC32_OUT(PC15))") (class "Default")
      (node (ref "BQ1") (pin "1") (pinfunction "1_1") (pintype "passive"))
      (node (ref "C16") (pin "1") (pinfunction "1_1") (pintype "passive"))
      (node (ref "D8") (pin "9") (pinfunction "PC15-OSC32_OUT(PC15)_9") (pintype "bidirectional"))
    )
    (net (code "87") (name "Net-(D8A-PH0-OSC_IN(PH0))") (class "Default")
      (node (ref "BQ2") (pin "2") (pinfunction "2_2") (pintype "passive"))
      (node (ref "C37") (pin "2") (pinfunction "2_2") (pintype "passive"))
      (node (ref "D8") (pin "12") (pinfunction "PH0-OSC_IN(PH0)_12") (pintype "bidirectional"))
      (node (ref "R30") (pin "2") (pinfunction "2_2") (pintype "passive"))
    )
    (net (code "88") (name "Net-(D8A-PH1-OSC_OUT(PH1))") (class "Default")
      (node (ref "BQ2") (pin "1") (pinfunction "1_1") (pintype "passive"))
      (node (ref "C38") (pin "1") (pinfunction "1_1") (pintype "passive"))
      (node (ref "D8") (pin "13") (pinfunction "PH1-OSC_OUT(PH1)_13") (pintype "bidirectional"))
      (node (ref "R30") (pin "1") (pinfunction "1_1") (pintype "passive"))
    )
    (net (code "89") (name "Net-(D8A-VCAP_1)") (class "Default")
      (node (ref "C34") (pin "2") (pinfunction "2_2") (pintype "passive"))
      (node (ref "D8") (pin "49") (pinfunction "VCAP_1_49") (pintype "power_in"))
    )
    (net (code "90") (name "Net-(D8A-VCAP_2)") (class "Default")
      (node (ref "C32") (pin "2") (pinfunction "2_2") (pintype "passive"))
      (node (ref "D8") (pin "73") (pinfunction "VCAP_2_73") (pintype "power_in"))
    )
    (net (code "91") (name "Net-(D8B-VBAT)") (class "Default")
      (node (ref "C35") (pin "2") (pinfunction "2_2") (pintype "passive"))
      (node (ref "D8") (pin "6") (pinfunction "VBAT_6") (pintype "power_in"))
      (node (ref "VD7") (pin "3") (pinfunction "C_3") (pintype "passive"))
    )
    (net (code "92") (name "Net-(D8B-VDDA)") (class "Default")
      (node (ref "C26") (pin "1") (pinfunction "1_1") (pintype "passive"))
      (node (ref "C30") (pin "1") (pinfunction "1_1") (pintype "passive"))
      (node (ref "D8") (pin "22") (pinfunction "VDDA_22") (pintype "power_in"))
      (node (ref "L2") (pin "2") (pinfunction "2_2") (pintype "passive"))
      (node (ref "R27") (pin "1") (pinfunction "1_1") (pintype "passive"))
    )
    (net (code "93") (name "Net-(D8B-VREF+)") (class "Default")
      (node (ref "C25") (pin "1") (pinfunction "1_1") (pintype "passive"))
      (node (ref "C29") (pin "2") (pinfunction "2_2") (pintype "passive"))
      (node (ref "D8") (pin "21") (pinfunction "VREF+_21") (pintype "power_in"))
      (node (ref "R27") (pin "2") (pinfunction "2_2") (pintype "passive"))
    )
    (net (code "94") (name "Net-(D9-C1+)") (class "Default")
      (node (ref "C17") (pin "1") (pinfunction "1_1") (pintype "passive"))
      (node (ref "D9") (pin "1") (pinfunction "C1+_1") (pintype "passive"))
    )
    (net (code "95") (name "Net-(D9-C1-)") (class "Default")
      (node (ref "C17") (pin "2") (pinfunction "2_2") (pintype "passive"))
      (node (ref "D9") (pin "3") (pinfunction "C1-_3") (pintype "passive"))
    )
    (net (code "96") (name "Net-(D9-C2+)") (class "Default")
      (node (ref "C18") (pin "1") (pinfunction "1_1") (pintype "passive"))
      (node (ref "D9") (pin "4") (pinfunction "C2+_4") (pintype "passive"))
    )
    (net (code "97") (name "Net-(D9-C2-)") (class "Default")
      (node (ref "C18") (pin "2") (pinfunction "2_2") (pintype "passive"))
      (node (ref "D9") (pin "5") (pinfunction "C2-_5") (pintype "passive"))
    )
    (net (code "98") (name "Net-(D9-V+)") (class "Default")
      (node (ref "C20") (pin "1") (pinfunction "1_1") (pintype "passive"))
      (node (ref "D9") (pin "2") (pinfunction "V+_2") (pintype "power_in"))
    )
    (net (code "99") (name "Net-(D9-V-)") (class "Default")
      (node (ref "C31") (pin "2") (pinfunction "2_2") (pintype "passive"))
      (node (ref "D9") (pin "6") (pinfunction "V-_6") (pintype "power_in"))
    )
    (net (code "100") (name "Net-(D10-COL{slash}PHYAD0)") (class "Default")
      (node (ref "D10") (pin "42") (pinfunction "COL/PHYAD0_42") (pintype "output"))
      (node (ref "R47") (pin "1") (pinfunction "1_1") (pintype "passive"))
    )
    (net (code "101") (name "Net-(D10-LED_SPEED{slash}AN1)") (class "Default")
      (node (ref "D10") (pin "27") (pinfunction "LED_SPEED/AN1_27") (pintype "output"))
      (node (ref "R52") (pin "1") (pinfunction "1_1") (pintype "passive"))
    )
    (net (code "102") (name "Net-(D10-PWR_DOWN{slash}INT)") (class "Default")
      (node (ref "D10") (pin "7") (pinfunction "PWR_DOWN/INT_7") (pintype "input"))
      (node (ref "R35") (pin "1") (pinfunction "1_1") (pintype "passive"))
    )
    (net (code "103") (name "Net-(D10-RBIAS)") (class "Default")
      (node (ref "D10") (pin "24") (pinfunction "RBIAS_24") (pintype "input"))
      (node (ref "R44") (pin "1") (pinfunction "1_1") (pintype "passive"))
    )
    (net (code "104") (name "Net-(D10-RESERVED)") (class "Default")
      (node (ref "D10") (pin "20") (pinfunction "RESERVED_20") (pintype "bidirectional"))
      (node (ref "R43") (pin "1") (pinfunction "1_1") (pintype "passive"))
    )
    (net (code "105") (name "Net-(D10-RESERVED_2)") (class "Default")
      (node (ref "D10") (pin "21") (pinfunction "RESERVED_2_21") (pintype "bidirectional"))
      (node (ref "R42") (pin "1") (pinfunction "1_1") (pintype "passive"))
    )
    (net (code "106") (name "Net-(D10-RX_DV{slash}MII_MODE)") (class "Default")
      (node (ref "D10") (pin "39") (pinfunction "RX_DV/MII_MODE_39") (pintype "output"))
      (node (ref "R46") (pin "1") (pinfunction "1_1") (pintype "passive"))
    )
    (net (code "107") (name "Net-(F1-Pad2)") (class "Default")
      (node (ref "F1") (pin "2") (pinfunction "2_2") (pintype "passive"))
      (node (ref "R4") (pin "1") (pinfunction "1_1") (pintype "passive"))
    )
    (net (code "108") (name "Net-(G1-Pad2)") (class "Default")
      (node (ref "G1") (pin "2") (pinfunction "2_2") (pintype "passive"))
      (node (ref "VT1") (pin "C") (pinfunction "C_C") (pintype "passive"))
    )
    (net (code "109") (name "Net-(HL1-A)") (class "Default")
      (node (ref "HL1") (pin "1") (pinfunction "A_1") (pintype "passive"))
      (node (ref "R8") (pin "2") (pinfunction "2_2") (pintype "passive"))
    )
    (net (code "110") (name "Net-(HL2-POS)") (class "Default")
      (node (ref "HL2") (pin "1") (pinfunction "POS_1") (pintype "passive"))
      (node (ref "R23") (pin "2") (pinfunction "2_2") (pintype "passive"))
    )
    (net (code "111") (name "Net-(HL3-POS)") (class "Default")
      (node (ref "HL3") (pin "1") (pinfunction "POS_1") (pintype "passive"))
      (node (ref "R24") (pin "2") (pinfunction "2_2") (pintype "passive"))
    )
    (net (code "112") (name "Net-(HL4-A)") (class "Default")
      (node (ref "HL4") (pin "1") (pinfunction "A_1") (pintype "passive"))
      (node (ref "R32") (pin "2") (pinfunction "2_2") (pintype "passive"))
    )
    (net (code "113") (name "Net-(HL5-A)") (class "Default")
      (node (ref "HL5") (pin "1") (pinfunction "A_1") (pintype "passive"))
      (node (ref "R33") (pin "2") (pinfunction "2_2") (pintype "passive"))
    )
    (net (code "114") (name "Net-(HL6-A)") (class "Default")
      (node (ref "HL6") (pin "1") (pinfunction "A_1") (pintype "passive"))
      (node (ref "R34") (pin "2") (pinfunction "2_2") (pintype "passive"))
    )
    (net (code "115") (name "Net-(R9-Pad2)") (class "Default")
      (node (ref "R9") (pin "2") (pinfunction "2_2") (pintype "passive"))
      (node (ref "X3") (pin "1") (pinfunction "1_1") (pintype "passive"))
    )
    (net (code "116") (name "Net-(R21-Pad1)") (class "Default")
      (node (ref "R21") (pin "1") (pinfunction "1_1") (pintype "passive"))
      (node (ref "X6") (pin "1") (pinfunction "1_1") (pintype "passive"))
    )
    (net (code "117") (name "Net-(R39-Pad2)") (class "Default")
      (node (ref "R39") (pin "2") (pinfunction "2_2") (pintype "passive"))
      (node (ref "VT1") (pin "B") (pinfunction "B_B") (pintype "passive"))
    )
    (net (code "118") (name "Net-(R44-Pad2)") (class "Default")
      (node (ref "R44") (pin "2") (pinfunction "2_2") (pintype "passive"))
      (node (ref "R51") (pin "1") (pinfunction "1_1") (pintype "passive"))
    )
    (net (code "119") (name "Net-(R51-Pad2)") (class "Default")
      (node (ref "R51") (pin "2") (pinfunction "2_2") (pintype "passive"))
      (node (ref "R53") (pin "1") (pinfunction "1_1") (pintype "passive"))
    )
    (net (code "120") (name "Net-(VD1-A)") (class "Default")
      (node (ref "R4") (pin "2") (pinfunction "2_2") (pintype "passive"))
      (node (ref "VD1") (pin "1") (pinfunction "A_1") (pintype "passive"))
      (node (ref "VD3") (pin "1") (pinfunction "POS_1") (pintype "passive"))
    )
    (net (code "121") (name "Net-(VD2-A)") (class "Default")
      (node (ref "F2") (pin "1") (pinfunction "1_1") (pintype "passive"))
      (node (ref "VD2") (pin "2") (pinfunction "A_2") (pintype "passive"))
      (node (ref "X1") (pin "1") (pinfunction "VBUS_1") (pintype "passive"))
    )
    (net (code "122") (name "Net-(VD7-A1)") (class "Default")
      (node (ref "J1") (pin "1") (pinfunction "POS_1") (pintype "passive"))
      (node (ref "J1") (pin "2") (pinfunction "POS_2") (pintype "passive"))
      (node (ref "VD7") (pin "1") (pinfunction "A1_1") (pintype "passive"))
    )
    (net (code "123") (name "Net-(X12-LA)") (class "Default")
      (node (ref "R69") (pin "1") (pinfunction "1_1") (pintype "passive"))
      (node (ref "X12") (pin "9") (pinfunction "LA_9") (pintype "passive"))
    )
    (net (code "124") (name "Net-(X12-RA)") (class "Default")
      (node (ref "R70") (pin "1") (pinfunction "1_1") (pintype "passive"))
      (node (ref "X12") (pin "12") (pinfunction "RA_12") (pintype "passive"))
    )
    (net (code "125") (name "SHLD") (class "Default")
      (node (ref "C53") (pin "2") (pinfunction "2_2") (pintype "passive"))
      (node (ref "R68") (pin "2") (pinfunction "2_2") (pintype "passive"))
      (node (ref "X1") (pin "6") (pinfunction "SH_6") (pintype "passive"))
      (node (ref "X1") (pin "7") (pinfunction "SH_7") (pintype "passive"))
      (node (ref "X1") (pin "8") (pinfunction "SH_8") (pintype "passive"))
      (node (ref "X1") (pin "9") (pinfunction "SH_9") (pintype "passive"))
      (node (ref "X12") (pin "S1") (pinfunction "S1_S1") (pintype "passive"))
      (node (ref "X12") (pin "S2") (pinfunction "S2_S2") (pintype "passive"))
      (node (ref "X4") (pin "10") (pinfunction "SHLD_10") (pintype "passive"))
      (node (ref "X4") (pin "11") (pinfunction "SHLD_11") (pintype "passive"))
      (node (ref "X4") (pin "12") (pinfunction "SHLD_12") (pintype "passive"))
      (node (ref "X4") (pin "9") (pinfunction "SHLD_9") (pintype "passive"))
      (node (ref "X5") (pin "10") (pinfunction "MH1_10") (pintype "passive"))
      (node (ref "X5") (pin "11") (pinfunction "MH2_11") (pintype "passive"))
      (node (ref "X7") (pin "10") (pinfunction "MH1_10") (pintype "passive"))
      (node (ref "X7") (pin "11") (pinfunction "MH2_11") (pintype "passive"))
    )
    (net (code "126") (name "VBUS") (class "Default")
      (node (ref "C1") (pin "2") (pinfunction "2_2") (pintype "passive"))
      (node (ref "D4") (pin "12") (pinfunction "VCC_12") (pintype "power_in"))
      (node (ref "F2") (pin "2") (pinfunction "2_2") (pintype "passive"))
      (node (ref "VD4") (pin "A") (pinfunction "A_A") (pintype "passive"))
    )
    (net (code "127") (name "VCC") (class "Default")
      (node (ref "F1") (pin "1") (pinfunction "1_1") (pintype "passive"))
      (node (ref "X2") (pin "1") (pinfunction "1_1") (pintype "passive"))
    )
    (net (code "128") (name "VCCIO") (class "Default")
      (node (ref "C9") (pin "2") (pinfunction "2_2") (pintype "passive"))
      (node (ref "D4") (pin "10") (pinfunction "3V3OUT_10") (pintype "output"))
      (node (ref "D4") (pin "11") (pinfunction "~{RESET}_11") (pintype "input"))
      (node (ref "D4") (pin "3") (pinfunction "VCCIO_3") (pintype "power_in"))
      (node (ref "R16") (pin "2") (pinfunction "2_2") (pintype "passive"))
      (node (ref "R19") (pin "2") (pinfunction "2_2") (pintype "passive"))
      (node (ref "R23") (pin "1") (pinfunction "1_1") (pintype "passive"))
      (node (ref "R24") (pin "1") (pinfunction "1_1") (pintype "passive"))
    )
    (net (code "129") (name "unconnected-(BQ3-STD_OP-Pad1)") (class "Default")
      (node (ref "BQ3") (pin "1") (pinfunction "STD_OP_1") (pintype "passive"))
    )
    (net (code "130") (name "unconnected-(D3-VREF-Pad5)") (class "Default")
      (node (ref "D3") (pin "5") (pinfunction "VREF_5") (pintype "output"))
    )
    (net (code "131") (name "unconnected-(D4-CBUS0-Pad15)") (class "Default")
      (node (ref "D4") (pin "15") (pinfunction "CBUS0_15") (pintype "bidirectional"))
    )
    (net (code "132") (name "unconnected-(D4-CBUS3-Pad16)") (class "Default")
      (node (ref "D4") (pin "16") (pinfunction "CBUS3_16") (pintype "bidirectional"))
    )
    (net (code "133") (name "unconnected-(D4-~{CTS}-Pad6)") (class "Default")
      (node (ref "D4") (pin "6") (pinfunction "~{CTS}_6") (pintype "input"))
    )
    (net (code "134") (name "unconnected-(D4-~{RTS}-Pad2)") (class "Default")
      (node (ref "D4") (pin "2") (pinfunction "~{RTS}_2") (pintype "output"))
    )
    (net (code "135") (name "unconnected-(D7-UOUT-Pad4)") (class "Default")
      (node (ref "D7") (pin "4") (pinfunction "UOUT_4") (pintype "output"))
    )
    (net (code "136") (name "unconnected-(D8A-PA0-WKUP(PA0)-Pad23)") (class "Default")
      (node (ref "D8") (pin "23") (pinfunction "PA0-WKUP(PA0)_23") (pintype "bidirectional"))
    )
    (net (code "137") (name "unconnected-(D8A-PA8-Pad67)") (class "Default")
      (node (ref "D8") (pin "67") (pinfunction "PA8_67") (pintype "bidirectional"))
    )
    (net (code "138") (name "unconnected-(D8A-PB1-Pad36)") (class "Default")
      (node (ref "D8") (pin "36") (pinfunction "PB1_36") (pintype "bidirectional"))
    )
    (net (code "139") (name "unconnected-(D8A-PB6-Pad92)") (class "Default")
      (node (ref "D8") (pin "92") (pinfunction "PB6_92") (pintype "bidirectional"))
    )
    (net (code "140") (name "unconnected-(D8A-PB7-Pad93)") (class "Default")
      (node (ref "D8") (pin "93") (pinfunction "PB7_93") (pintype "bidirectional"))
    )
    (net (code "141") (name "unconnected-(D8A-PB14-Pad53)") (class "Default")
      (node (ref "D8") (pin "53") (pinfunction "PB14_53") (pintype "bidirectional"))
    )
    (net (code "142") (name "unconnected-(D8A-PB15-Pad54)") (class "Default")
      (node (ref "D8") (pin "54") (pinfunction "PB15_54") (pintype "bidirectional"))
    )
    (net (code "143") (name "unconnected-(D8A-PC0-Pad15)") (class "Default")
      (node (ref "D8") (pin "15") (pinfunction "PC0_15") (pintype "bidirectional"))
    )
    (net (code "144") (name "unconnected-(D8A-PC2-Pad17)") (class "Default")
      (node (ref "D8") (pin "17") (pinfunction "PC2_17") (pintype "bidirectional"))
    )
    (net (code "145") (name "unconnected-(D8A-PC3-Pad18)") (class "Default")
      (node (ref "D8") (pin "18") (pinfunction "PC3_18") (pintype "bidirectional"))
    )
    (net (code "146") (name "unconnected-(D8A-PC13-Pad7)") (class "Default")
      (node (ref "D8") (pin "7") (pinfunction "PC13_7") (pintype "bidirectional"))
    )
    (net (code "147") (name "unconnected-(D8A-PD0-Pad81)") (class "Default")
      (node (ref "D8") (pin "81") (pinfunction "PD0_81") (pintype "bidirectional"))
    )
    (net (code "148") (name "unconnected-(D8A-PD1-Pad82)") (class "Default")
      (node (ref "D8") (pin "82") (pinfunction "PD1_82") (pintype "bidirectional"))
    )
    (net (code "149") (name "unconnected-(D8A-PE1-Pad98)") (class "Default")
      (node (ref "D8") (pin "98") (pinfunction "PE1_98") (pintype "bidirectional"))
    )
    (net (code "150") (name "unconnected-(D8A-PE6-Pad5)") (class "Default")
      (node (ref "D8") (pin "5") (pinfunction "PE6_5") (pintype "bidirectional"))
    )
    (net (code "151") (name "unconnected-(D8A-PE9-Pad40)") (class "Default")
      (node (ref "D8") (pin "40") (pinfunction "PE9_40") (pintype "bidirectional"))
    )
    (net (code "152") (name "unconnected-(D8A-PE10-Pad41)") (class "Default")
      (node (ref "D8") (pin "41") (pinfunction "PE10_41") (pintype "bidirectional"))
    )
    (net (code "153") (name "unconnected-(D8A-PE11-Pad42)") (class "Default")
      (node (ref "D8") (pin "42") (pinfunction "PE11_42") (pintype "bidirectional"))
    )
    (net (code "154") (name "unconnected-(D8A-PE13-Pad44)") (class "Default")
      (node (ref "D8") (pin "44") (pinfunction "PE13_44") (pintype "bidirectional"))
    )
    (net (code "155") (name "unconnected-(D8A-PE14-Pad45)") (class "Default")
      (node (ref "D8") (pin "45") (pinfunction "PE14_45") (pintype "bidirectional"))
    )
    (net (code "156") (name "unconnected-(D8A-PE15-Pad46)") (class "Default")
      (node (ref "D8") (pin "46") (pinfunction "PE15_46") (pintype "bidirectional"))
    )
    (net (code "157") (name "unconnected-(D9-R2IN-Pad8)") (class "Default")
      (node (ref "D9") (pin "8") (pinfunction "R2IN_8") (pintype "passive"))
    )
    (net (code "158") (name "unconnected-(D9-R2OUT-Pad9)") (class "Default")
      (node (ref "D9") (pin "9") (pinfunction "R2OUT_9") (pintype "passive"))
    )
    (net (code "159") (name "unconnected-(D9-T2IN-Pad10)") (class "Default")
      (node (ref "D9") (pin "10") (pinfunction "T2IN_10") (pintype "passive"))
    )
    (net (code "160") (name "unconnected-(D9-T2OUT-Pad7)") (class "Default")
      (node (ref "D9") (pin "7") (pinfunction "T2OUT_7") (pintype "passive"))
    )
    (net (code "161") (name "unconnected-(D10-25MHZ_OUT-Pad25)") (class "Default")
      (node (ref "D10") (pin "25") (pinfunction "25MHZ_OUT_25") (pintype "output"))
    )
    (net (code "162") (name "unconnected-(D10-RXD_2{slash}PHYAD3-Pad45)") (class "Default")
      (node (ref "D10") (pin "45") (pinfunction "RXD_2/PHYAD3_45") (pintype "output"))
    )
    (net (code "163") (name "unconnected-(D10-RXD_3{slash}PHYAD4-Pad46)") (class "Default")
      (node (ref "D10") (pin "46") (pinfunction "RXD_3/PHYAD4_46") (pintype "output"))
    )
    (net (code "164") (name "unconnected-(D10-RX_CLK-Pad38)") (class "Default")
      (node (ref "D10") (pin "38") (pinfunction "RX_CLK_38") (pintype "output"))
    )
    (net (code "165") (name "unconnected-(D10-RX_ER{slash}MDIX_EN-Pad41)") (class "Default")
      (node (ref "D10") (pin "41") (pinfunction "RX_ER/MDIX_EN_41") (pintype "output"))
    )
    (net (code "166") (name "unconnected-(D10-TCK-Pad8)") (class "Default")
      (node (ref "D10") (pin "8") (pinfunction "TCK_8") (pintype "input"))
    )
    (net (code "167") (name "unconnected-(D10-TDI-Pad12)") (class "Default")
      (node (ref "D10") (pin "12") (pinfunction "TDI_12") (pintype "input"))
    )
    (net (code "168") (name "unconnected-(D10-TDO-Pad9)") (class "Default")
      (node (ref "D10") (pin "9") (pinfunction "TDO_9") (pintype "output"))
    )
    (net (code "169") (name "unconnected-(D10-TMS-Pad10)") (class "Default")
      (node (ref "D10") (pin "10") (pinfunction "TMS_10") (pintype "input"))
    )
    (net (code "170") (name "unconnected-(D10-TRST-Pad11)") (class "Default")
      (node (ref "D10") (pin "11") (pinfunction "TRST_11") (pintype "input"))
    )
    (net (code "171") (name "unconnected-(D10-TXD_2-Pad5)") (class "Default")
      (node (ref "D10") (pin "5") (pinfunction "TXD_2_5") (pintype "input"))
    )
    (net (code "172") (name "unconnected-(D10-TXD_3{slash}SNI_MODE-Pad6)") (class "Default")
      (node (ref "D10") (pin "6") (pinfunction "TXD_3/SNI_MODE_6") (pintype "input"))
    )
    (net (code "173") (name "unconnected-(D10-TX_CLK-Pad1)") (class "Default")
      (node (ref "D10") (pin "1") (pinfunction "TX_CLK_1") (pintype "output"))
    )
    (net (code "174") (name "unconnected-(D10-X2-Pad33)") (class "Default")
      (node (ref "D10") (pin "33") (pinfunction "X2_33") (pintype "output"))
    )
    (net (code "175") (name "unconnected-(VD5-A-Pad2)") (class "Default")
      (node (ref "VD5") (pin "2") (pinfunction "A_2") (pintype "passive"))
    )
    (net (code "176") (name "unconnected-(X1-ID-Pad4)") (class "Default")
      (node (ref "X1") (pin "4") (pinfunction "ID_4") (pintype "passive"))
    )
    (net (code "177") (name "unconnected-(X5-Pad4)") (class "Default")
      (node (ref "X5") (pin "4") (pinfunction "4_4") (pintype "passive"))
    )
    (net (code "178") (name "unconnected-(X5-Pad6)") (class "Default")
      (node (ref "X5") (pin "6") (pinfunction "6_6") (pintype "passive"))
    )
    (net (code "179") (name "unconnected-(X5-Pad8)") (class "Default")
      (node (ref "X5") (pin "8") (pinfunction "8_8") (pintype "passive"))
    )
    (net (code "180") (name "unconnected-(X7-Pad6)") (class "Default")
      (node (ref "X7") (pin "6") (pinfunction "6_6") (pintype "passive"))
    )
    (net (code "181") (name "unconnected-(X7-Pad7)") (class "Default")
      (node (ref "X7") (pin "7") (pinfunction "7_7") (pintype "passive"))
    )
    (net (code "182") (name "unconnected-(X7-Pad8)") (class "Default")
      (node (ref "X7") (pin "8") (pinfunction "8_8") (pintype "passive"))
    )
    (net (code "183") (name "unconnected-(X12-NC-Pad7)") (class "Default")
      (node (ref "X12") (pin "7") (pinfunction "NC_7") (pintype "passive"))
    )
  )
)
